# design.net
KiCad netlist of a schematic drawn in Altium Designer
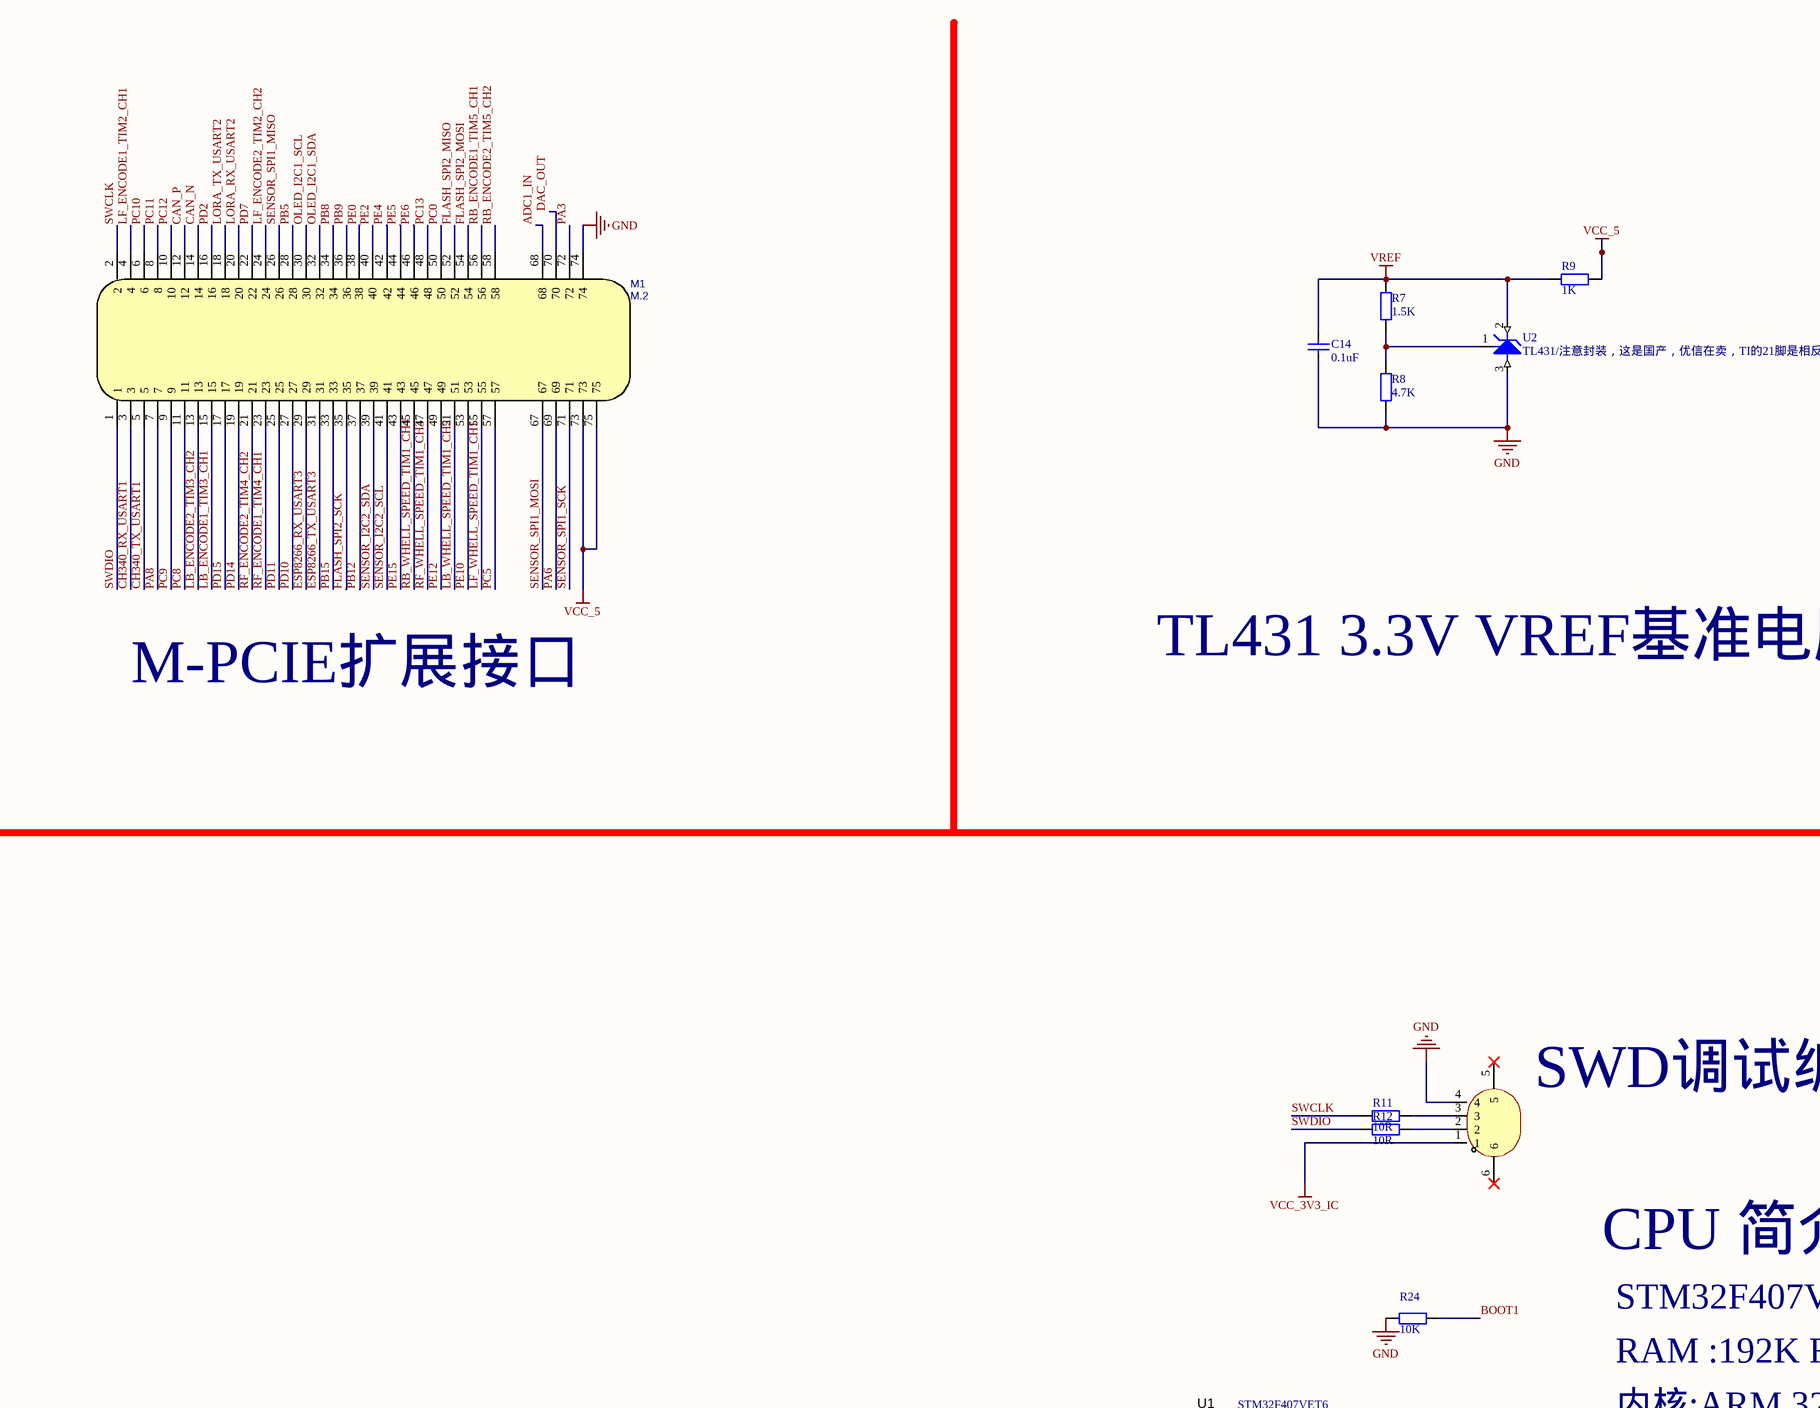
[diagram p0: 主控及低压电源.SchDoc, top left]
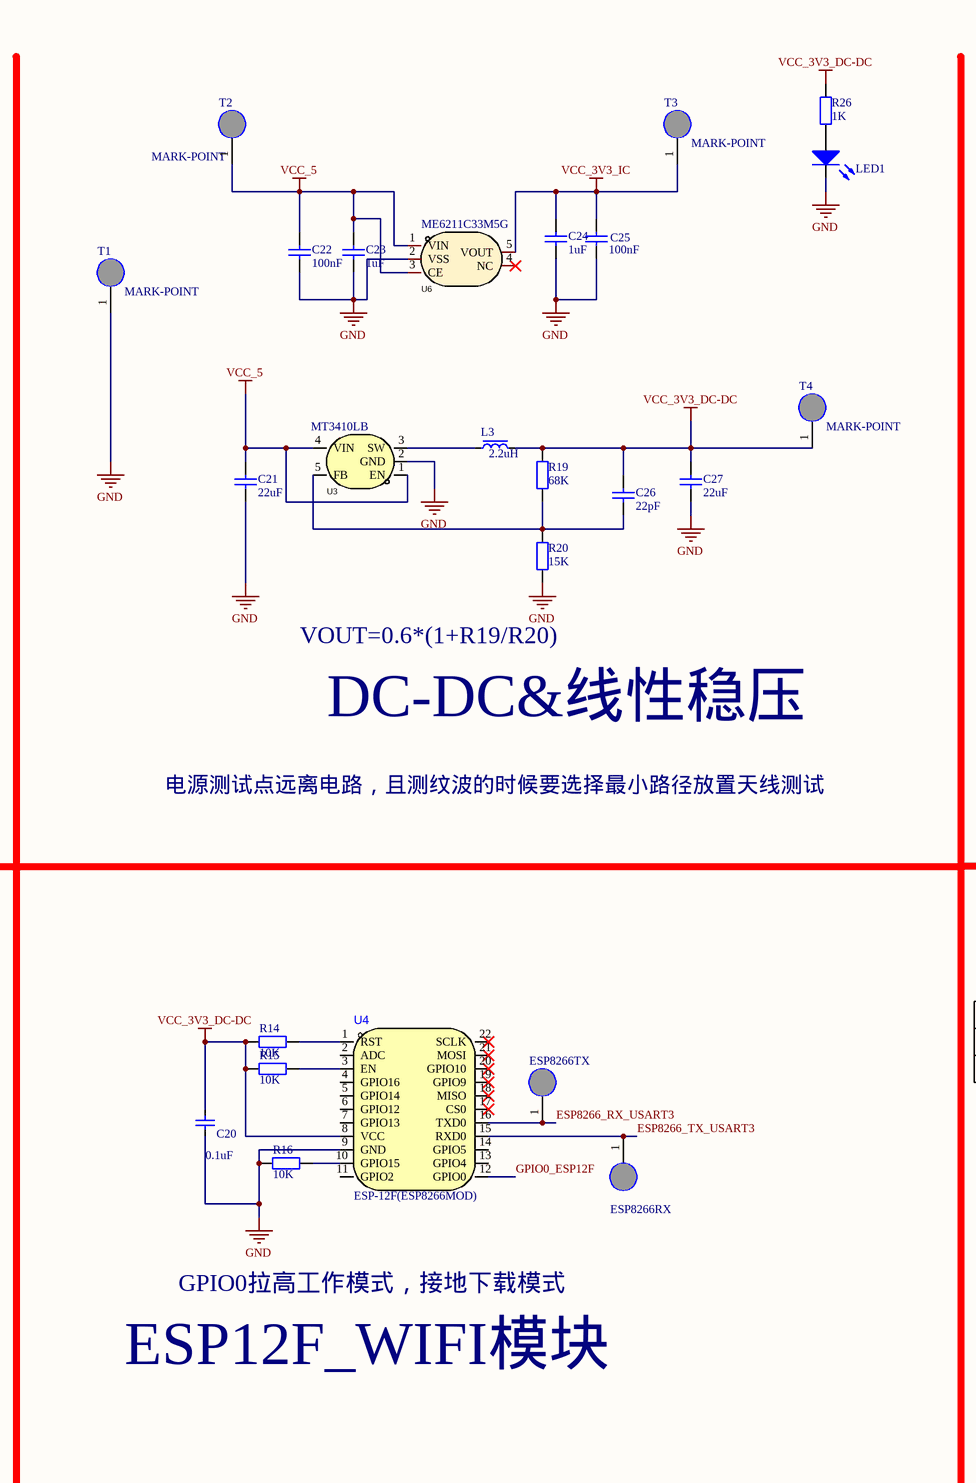
[diagram p1: 主控及低压电源.SchDoc, top middle]
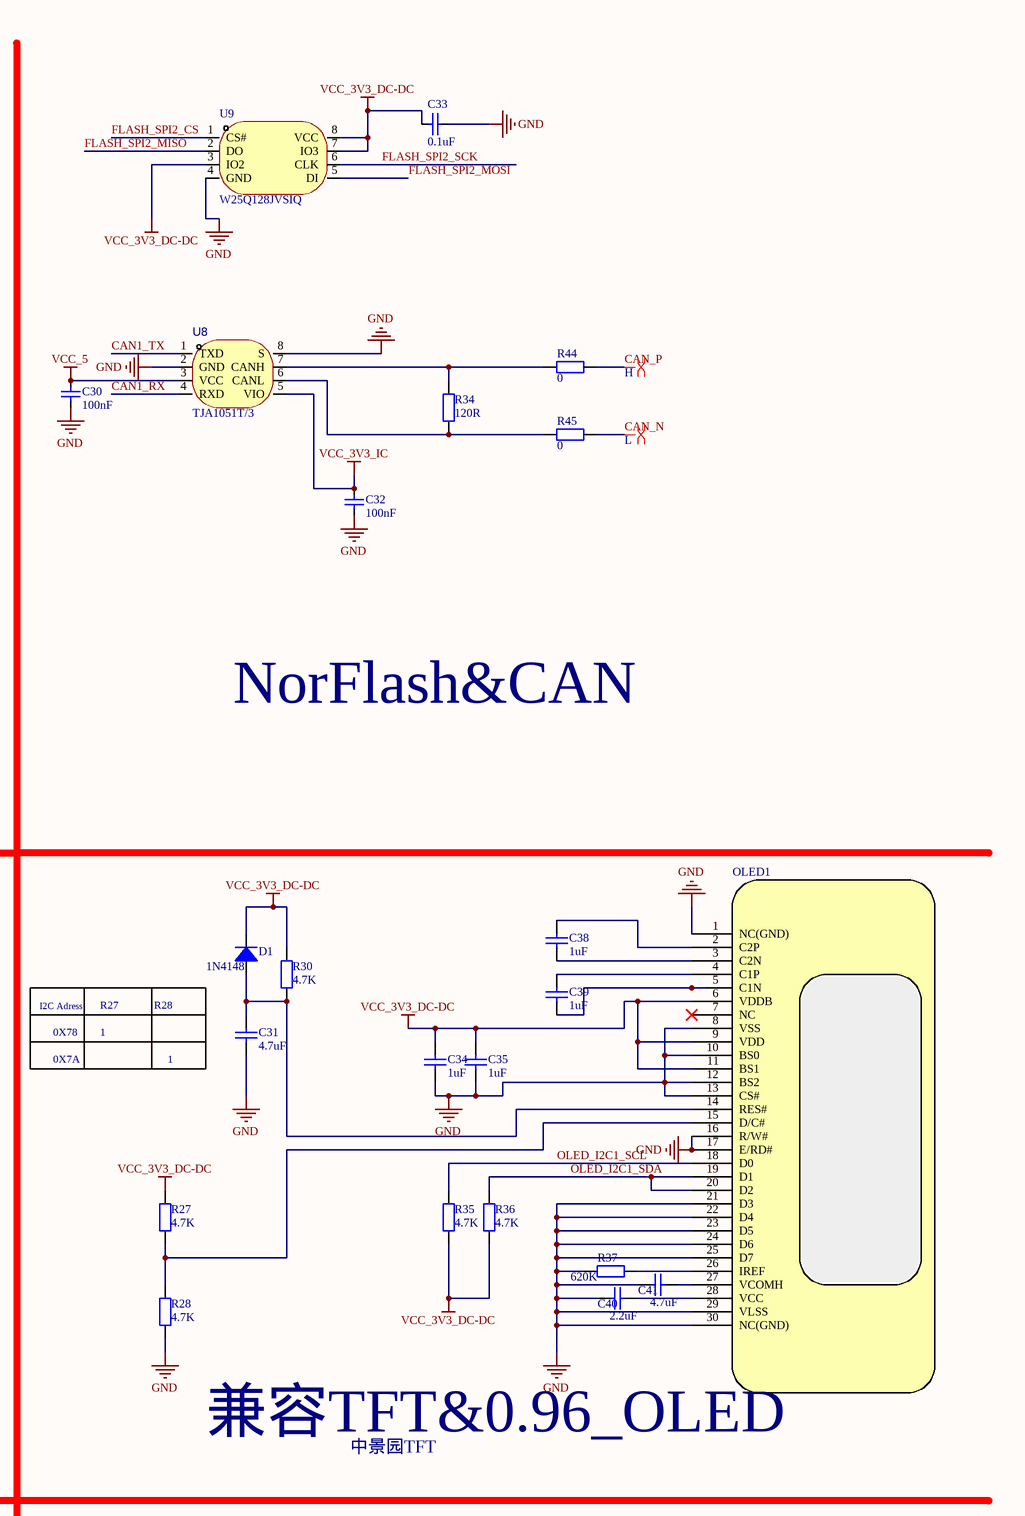
[diagram p2: 主控及低压电源.SchDoc, top right]
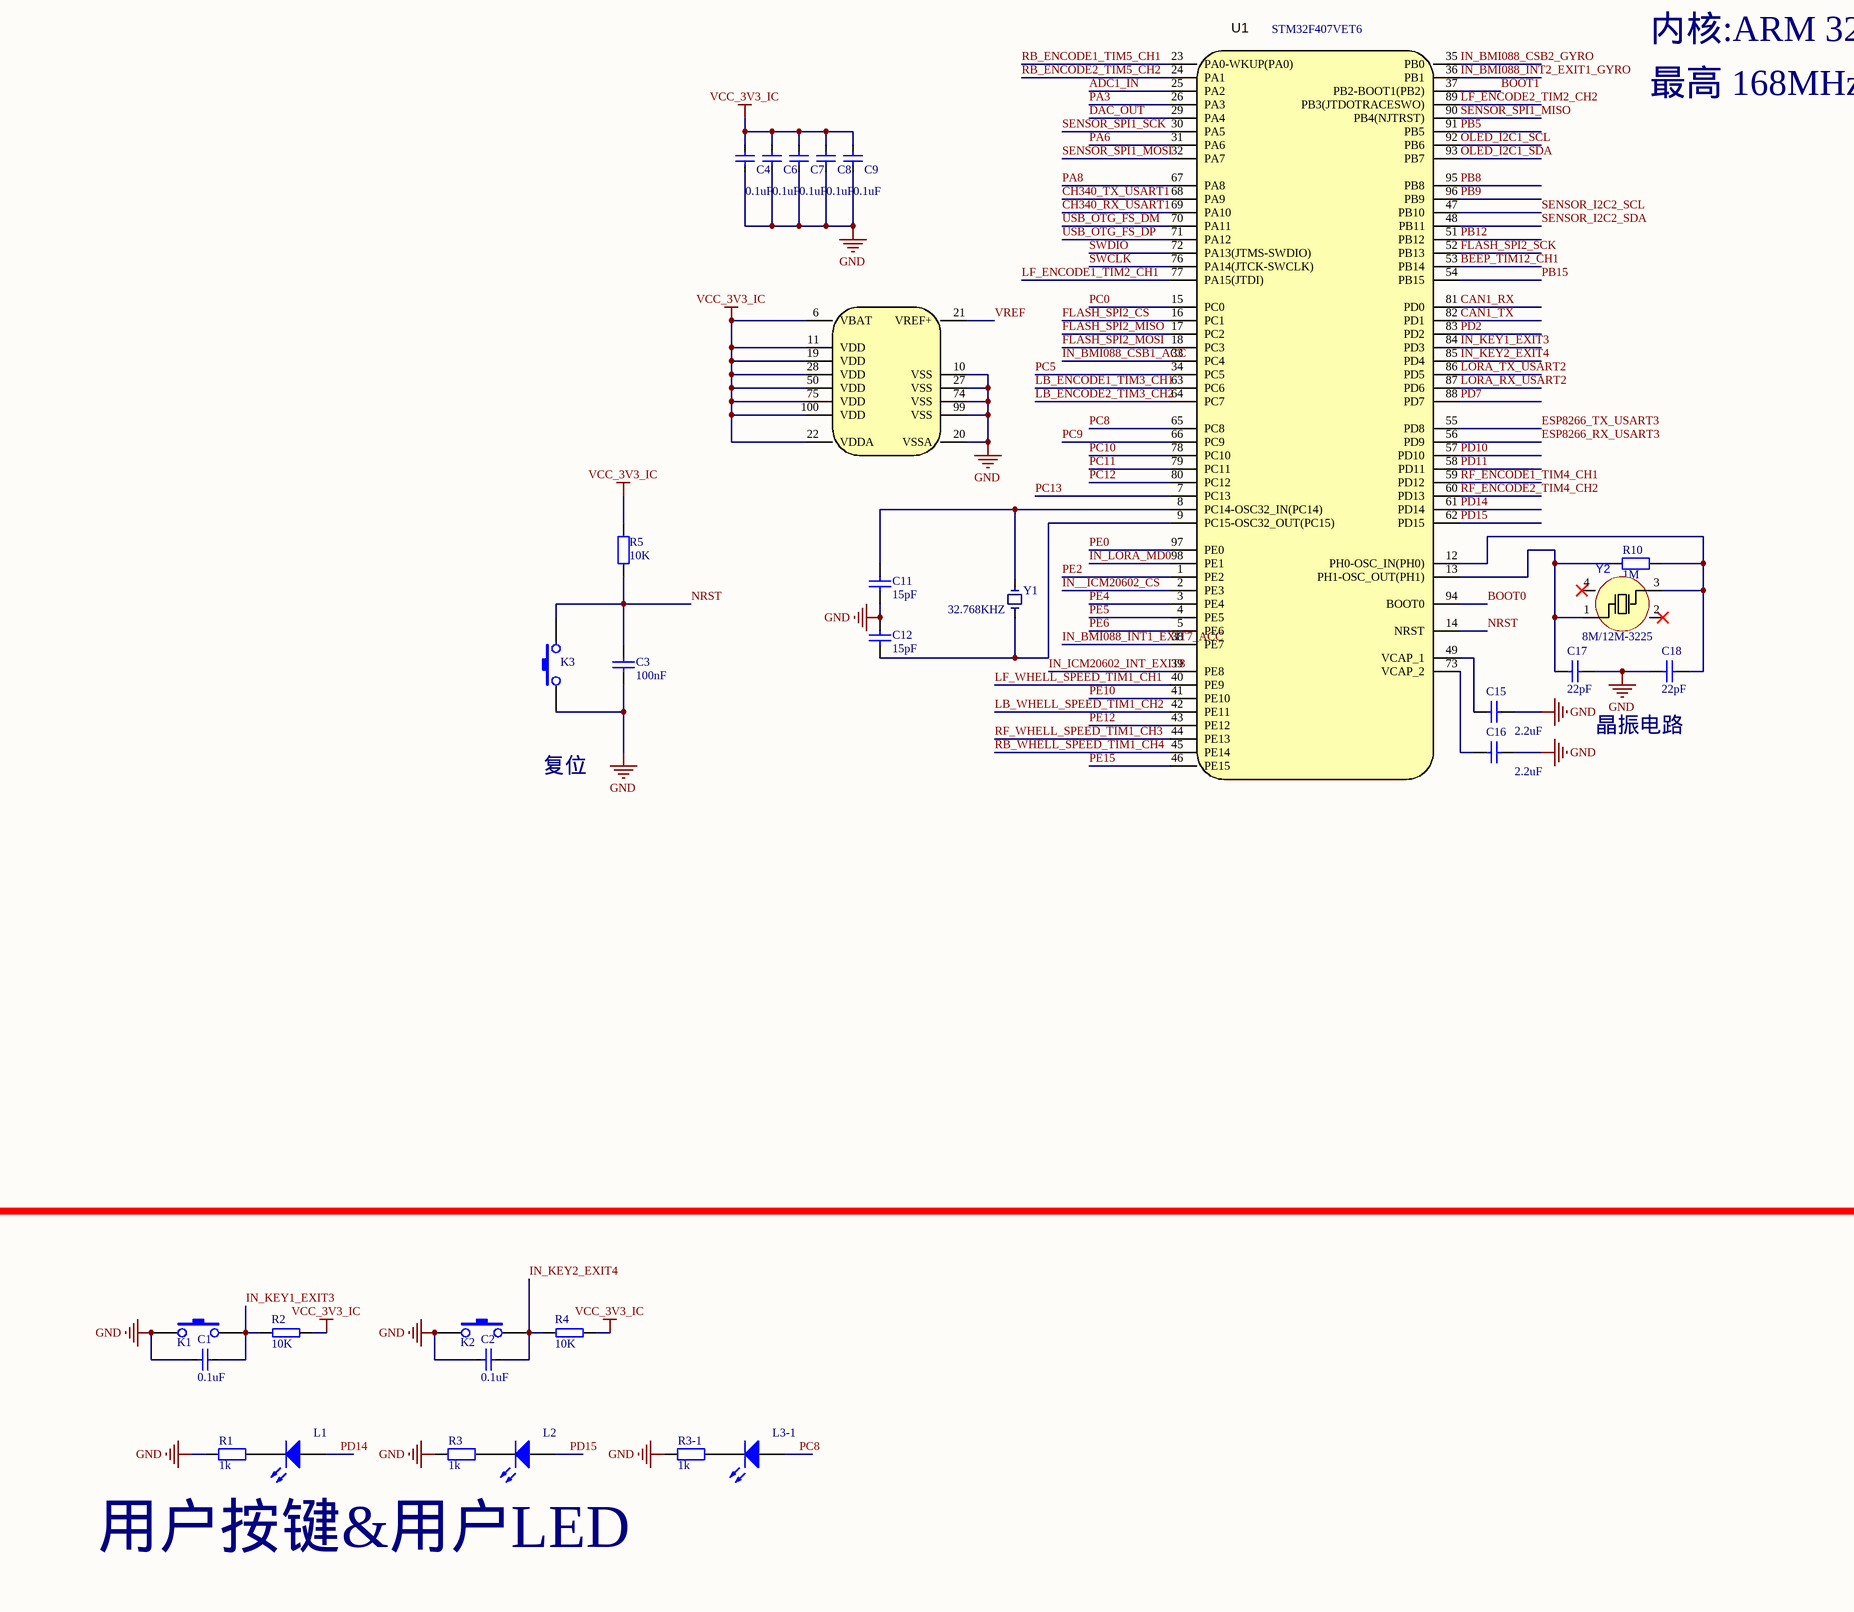
[diagram p3: 主控及低压电源.SchDoc, bottom left]
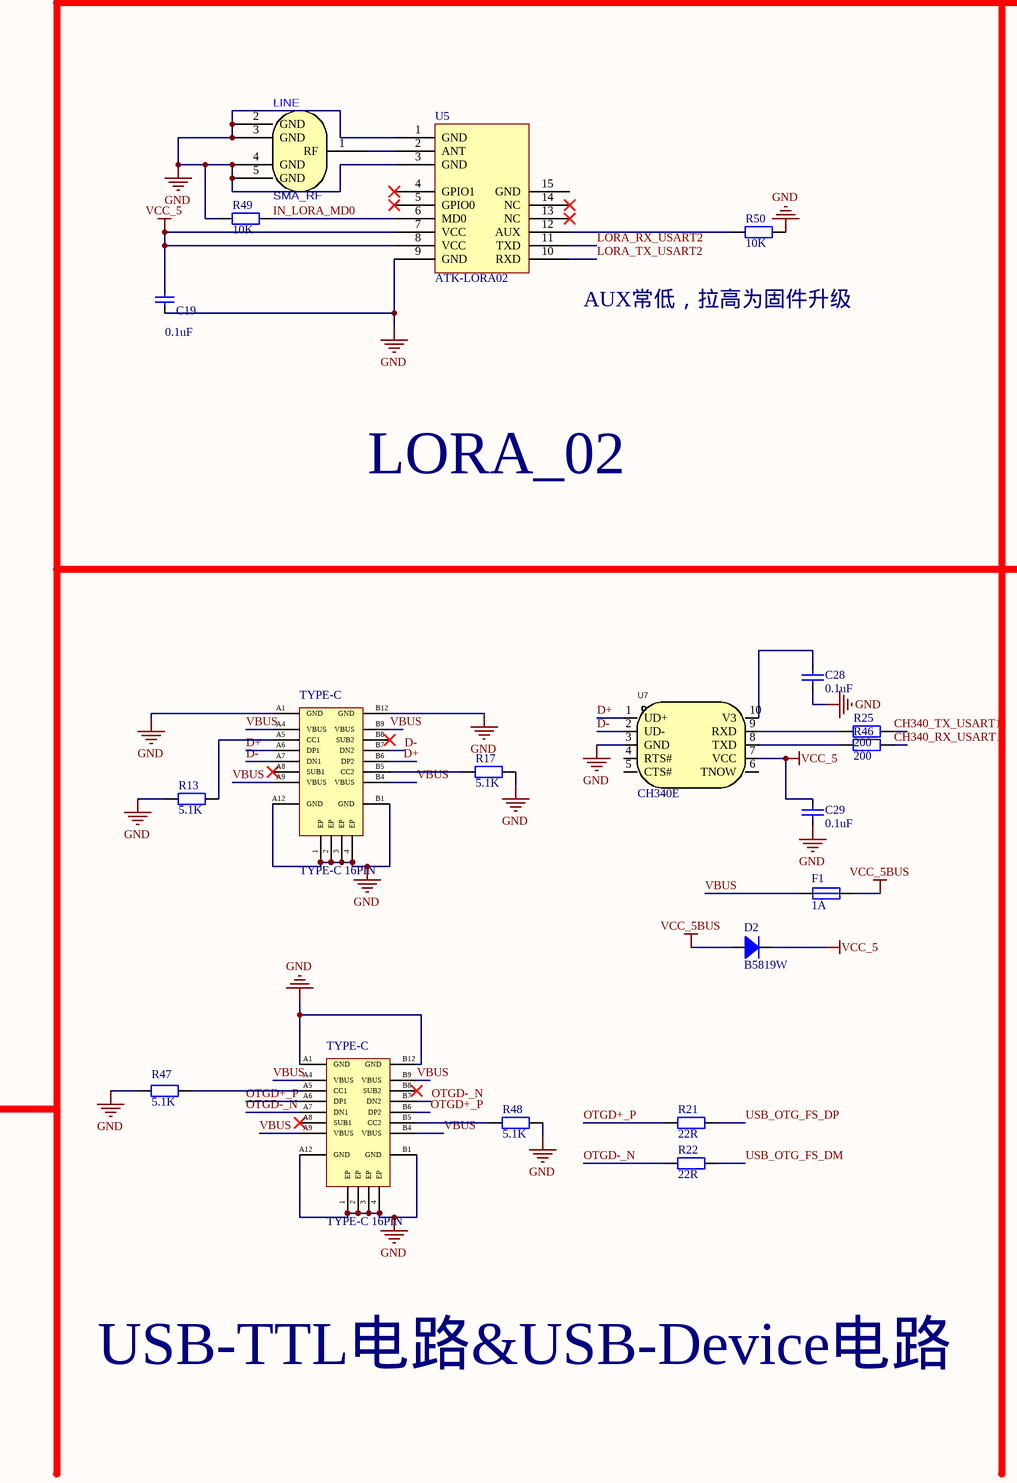
[diagram p4: 主控及低压电源.SchDoc, bottom middle]
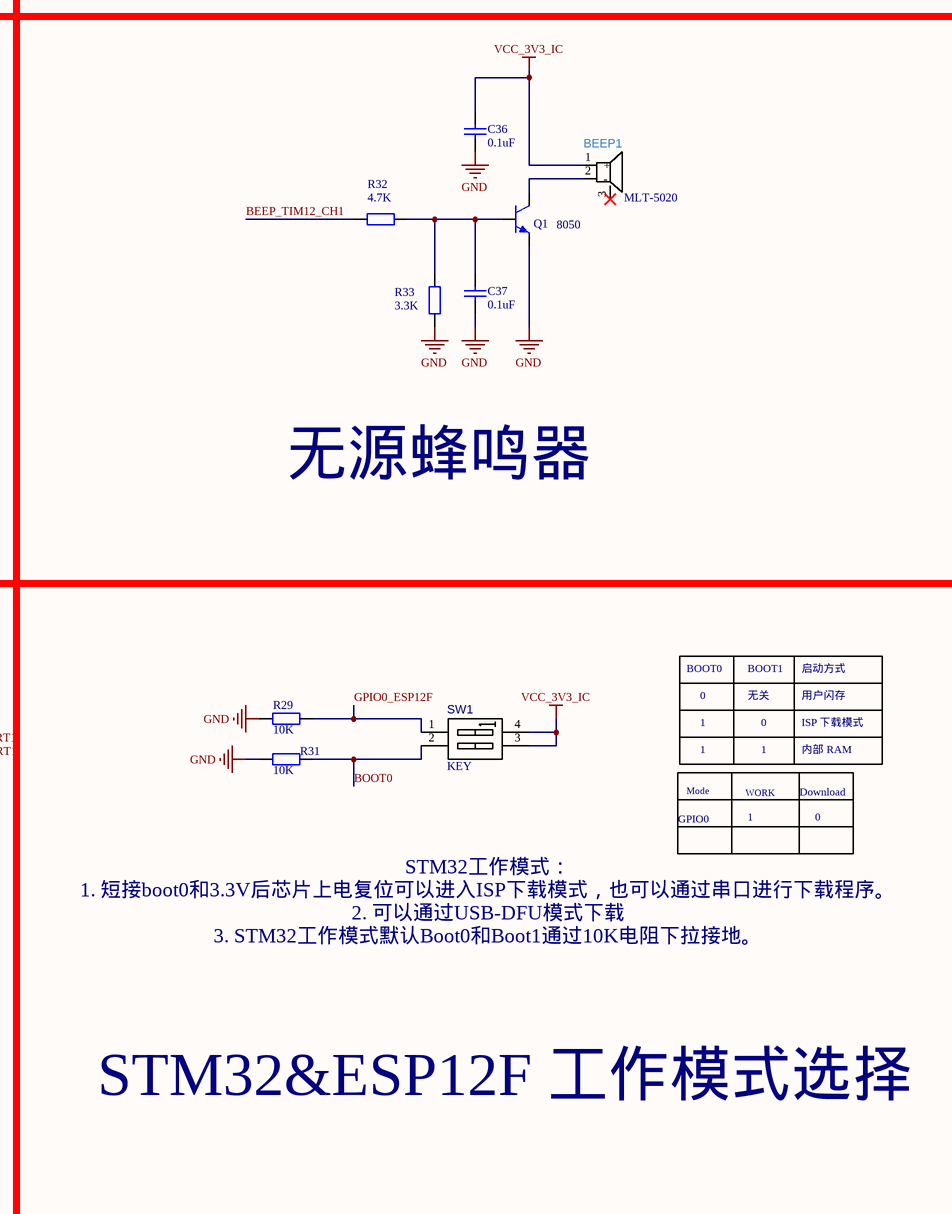
[diagram p5: 主控及低压电源.SchDoc, bottom right]

(export (version "E")
  (design (tool "Eeschema 10.0.6"))
  (components
    (comp (ref "1")
      (value "TYPE-C 16PIN")
      (footprint "TYPE-C 16PIN")
      (libsource (lib "IPC14") (part "TYPE-C 16PIN"))
    )
    (comp (ref "2")
      (value "TYPE-C 16PIN")
      (footprint "TYPE-C 16PIN")
      (libsource (lib "IPC14") (part "TYPE-C 16PIN"))
    )
    (comp (ref "BEEP1")
      (value "MLT-5020")
      (footprint "BUZ-SMD_L5.0-W5.5-P4.60")
      (fields (field (name "MANUFACTURER") "华能"))
      (libsource (lib "KESHE") (part "MLT-5020"))
    )
    (comp (ref "C1")
      (value "0.1uF")
      (footprint "0805_C")
      (description "Capacitor")
      (libsource (lib "SCH_Passive") (part "Cap_0603"))
    )
    (comp (ref "C2")
      (value "0.1uF")
      (footprint "0805_C")
      (description "Capacitor")
      (libsource (lib "SCH_Passive") (part "Cap_0603"))
    )
    (comp (ref "C3")
      (value "100nF")
      (footprint "0603_C")
      (description "Capacitor")
      (libsource (lib "IPC14") (part "CAP"))
    )
    (comp (ref "C4") (value "0.1uF") (footprint "0603_C") (libsource (lib "IPC14(1)") (part "CAP1")))
    (comp (ref "C6") (value "0.1uF") (footprint "0603_C") (libsource (lib "IPC14(1)") (part "CAP1")))
    (comp (ref "C7") (value "0.1uF") (footprint "0603_C") (libsource (lib "IPC14(1)") (part "CAP1")))
    (comp (ref "C8") (value "0.1uF") (footprint "0603_C") (libsource (lib "IPC14(1)") (part "CAP1")))
    (comp (ref "C9") (value "0.1uF") (footprint "0603_C") (libsource (lib "IPC14(1)") (part "CAP1")))
    (comp (ref "C11")
      (value "15pF")
      (footprint "0603_C")
      (description "Capacitor")
      (libsource (lib "IPC14") (part "CAP"))
    )
    (comp (ref "C12")
      (value "15pF")
      (footprint "0603_C")
      (description "Capacitor")
      (libsource (lib "IPC14") (part "CAP"))
    )
    (comp (ref "C14")
      (value "0.1uF")
      (footprint "0603_C")
      (description "Capacitor")
      (libsource (lib "SCH_Passive") (part "Cap_0805"))
    )
    (comp (ref "C15")
      (value "2.2uF")
      (footprint "0603_C")
      (description "Capacitor")
      (libsource (lib "IPC14") (part "CAP"))
    )
    (comp (ref "C16")
      (value "2.2uF")
      (footprint "0603_C")
      (description "Capacitor")
      (libsource (lib "IPC14") (part "CAP"))
    )
    (comp (ref "C17")
      (value "22pF")
      (footprint "0603_C")
      (description "Capacitor")
      (libsource (lib "IPC14") (part "CAP"))
    )
    (comp (ref "C18")
      (value "22pF")
      (footprint "0603_C")
      (description "Capacitor")
      (libsource (lib "IPC14") (part "CAP"))
    )
    (comp (ref "C19") (value "0.1uF") (footprint "0603_C") (libsource (lib "IPC14(1)") (part "CAP1")))
    (comp (ref "C20") (value "0.1uF") (footprint "0603_C") (libsource (lib "IPC14(1)") (part "CAP1")))
    (comp (ref "C21")
      (value "22uF")
      (footprint "0603_C")
      (description "Capacitor")
      (libsource (lib "IPC14") (part "CAP"))
    )
    (comp (ref "C22")
      (value "100nF")
      (footprint "0805C")
      (description "Capacitor")
      (libsource (lib "IPC14") (part "CAP"))
    )
    (comp (ref "C23")
      (value "1uF")
      (footprint "0805_C")
      (description "Capacitor")
      (libsource (lib "IPC14") (part "CAP"))
    )
    (comp (ref "C24")
      (value "1uF")
      (footprint "0805_C")
      (description "Capacitor")
      (libsource (lib "IPC14") (part "CAP"))
    )
    (comp (ref "C25")
      (value "100nF")
      (footprint "0805C")
      (description "Capacitor")
      (libsource (lib "IPC14") (part "CAP"))
    )
    (comp (ref "C26")
      (value "22pF")
      (footprint "0603_C")
      (description "Capacitor")
      (libsource (lib "IPC14") (part "CAP"))
    )
    (comp (ref "C27")
      (value "22uF")
      (footprint "1206_C")
      (description "Capacitor")
      (libsource (lib "IPC14") (part "CAP"))
    )
    (comp (ref "C28")
      (value "0.1uF")
      (footprint "0603_C")
      (description "Capacitor")
      (libsource (lib "SCH_Passive") (part "Cap_0805"))
    )
    (comp (ref "C29")
      (value "0.1uF")
      (footprint "0603_C")
      (description "Capacitor")
      (libsource (lib "SCH_Passive") (part "Cap_0805"))
    )
    (comp (ref "C30") (value "100nF") (footprint "0603_C") (libsource (lib "IPC14(1)") (part "CAP1")))
    (comp (ref "C31")
      (value "4.7uF")
      (footprint "0603_C")
      (description "Capacitor")
      (libsource (lib "IPC14") (part "CAP"))
    )
    (comp (ref "C32") (value "100nF") (footprint "0603_C") (libsource (lib "IPC14(1)") (part "CAP1")))
    (comp (ref "C33")
      (value "0.1uF")
      (footprint "0603_C")
      (description "Capacitor")
      (libsource (lib "SCH_Passive") (part "Cap_0603"))
    )
    (comp (ref "C34")
      (value "1uF")
      (footprint "0603_C")
      (description "Capacitor")
      (libsource (lib "IPC14") (part "CAP"))
    )
    (comp (ref "C35")
      (value "1uF")
      (footprint "0603_C")
      (description "Capacitor")
      (libsource (lib "IPC14") (part "CAP"))
    )
    (comp (ref "C36")
      (value "0.1uF")
      (footprint "0603_C")
      (description "Capacitor")
      (libsource (lib "IPC14") (part "CAP"))
    )
    (comp (ref "C37")
      (value "0.1uF")
      (footprint "0603_C")
      (description "Capacitor")
      (libsource (lib "IPC14") (part "CAP"))
    )
    (comp (ref "C38")
      (value "1uF")
      (footprint "0603_C")
      (description "Capacitor")
      (libsource (lib "IPC14") (part "CAP"))
    )
    (comp (ref "C39")
      (value "1uF")
      (footprint "0603_C")
      (description "Capacitor")
      (libsource (lib "IPC14") (part "CAP"))
    )
    (comp (ref "C40")
      (value "2.2uF")
      (footprint "0603_C")
      (description "Capacitor")
      (libsource (lib "IPC14") (part "CAP"))
    )
    (comp (ref "C41")
      (value "4.7uF")
      (footprint "0603_C")
      (description "Capacitor")
      (libsource (lib "IPC14") (part "CAP"))
    )
    (comp (ref "D1") (value "1N4148") (footprint "SOD123") (libsource (lib "IPC14") (part "1N4007")))
    (comp (ref "D2") (value "B5819W") (footprint "SOD123") (libsource (lib "IPC14") (part "1N4007")))
    (comp (ref "ESP8266RX")
      (value "MARK-POINT")
      (footprint "MARK-POINT")
      (libsource (lib "KESHE") (part "MARK-POINT"))
    )
    (comp (ref "ESP8266TX")
      (value "MARK-POINT")
      (footprint "MARK-POINT")
      (libsource (lib "KESHE") (part "MARK-POINT"))
    )
    (comp (ref "F1")
      (value "1A")
      (footprint "FUSE_1206")
      (description "FUSE,Littelfuse")
      (fields (field (name "Comment") "Fuse 1"))
      (libsource (lib "xl_lib_v2") (part "Fuse 1"))
    )
    (comp (ref "J1")
      (value "XH-4P卧贴")
      (footprint "CONN-SMD_2.54-4P-WT")
      (fields (field (name "MANUFACTURER") "BOOMELE(博穆精密)"))
      (libsource (lib "KESHE") (part "XH-4P卧贴"))
    )
    (comp (ref "K1") (value "SW-PB") (footprint "IPC14:key-sop") (libsource (lib "SW开关") (part "SW-PB")))
    (comp (ref "K2") (value "SW-PB") (footprint "IPC14:key-sop") (libsource (lib "SW开关") (part "SW-PB")))
    (comp (ref "K3") (value "SW-PB") (footprint "IPC14:key-sop") (libsource (lib "SW开关") (part "SW-PB")))
    (comp (ref "L1")
      (value "LED0")
      (footprint "0603_LED")
      (description "Typical INFRARED GaAs LED")
      (fields (field (name "PUBLISHER") "Altium Limited"))
      (libsource (lib "Miscellaneous Devices") (part "LED0"))
    )
    (comp (ref "L2")
      (value "LED0")
      (footprint "0603_LED")
      (description "Typical INFRARED GaAs LED")
      (fields (field (name "PUBLISHER") "Altium Limited"))
      (libsource (lib "Miscellaneous Devices") (part "LED0"))
    )
    (comp (ref "L3")
      (value "2.2uH")
      (footprint "SMD")
      (fields (field (name "ALTIUM_UNNAMED_1") "2.2uH"))
      (libsource (lib "电感-SCH") (part "INDUCTANCE"))
    )
    (comp (ref "L3-1")
      (value "LED0")
      (footprint "0603_LED")
      (description "Typical INFRARED GaAs LED")
      (fields (field (name "PUBLISHER") "Altium Limited"))
      (libsource (lib "Miscellaneous Devices") (part "LED0"))
    )
    (comp (ref "LED1")
      (value "LED_0603_BLUE")
      (footprint "0603_LED")
      (description "LED")
      (libsource (lib "IPC14(1)") (part "LED_0603_BLUE"))
    )
    (comp (ref "LINE") (value "SMA_RF") (footprint "SMA_RF偏脚") (libsource (lib "KESHE") (part "SMA_RF")))
    (comp (ref "M1")
      (value "M.2")
      (footprint "M.2 M")
      (fields (field (name "CONTRIBUTOR") "LAXXI"))
      (libsource (lib "KESHE") (part "M.2"))
    )
    (comp (ref "OLED1")
      (value "OLED_0.96_30P")
      (footprint "oled_0.96_30p")
      (fields (field (name "MANUFACTURER") "WiseChip") (field (name "MANUFACTURER PART") "VG-2864KSWEG01"))
      (libsource (lib "KESHE") (part "OLED_0.96_30P"))
    )
    (comp (ref "Q1")
      (value "8050")
      (footprint "SOT_23")
      (description "NPN")
      (libsource (lib "xl_lib_v1") (part "S8050"))
    )
    (comp (ref "R1")
      (value "1k")
      (footprint "0603_R")
      (description "Resistor")
      (fields (field (name "Comment") "1K") (field (name "PUBLISHER") "Altium Limited"))
      (libsource (lib "Miscellaneous Devices") (part "Res2"))
    )
    (comp (ref "R2")
      (value "10K")
      (footprint "0603_R")
      (fields (field (name "ALTIUM_UNNAMED_1") "10K"))
      (libsource (lib "Flyking 常用元件") (part "RES_10K"))
    )
    (comp (ref "R3")
      (value "1k")
      (footprint "0603_R")
      (description "Resistor")
      (fields (field (name "Comment") "1K") (field (name "PUBLISHER") "Altium Limited"))
      (libsource (lib "Miscellaneous Devices") (part "Res2"))
    )
    (comp (ref "R3-1")
      (value "1k")
      (footprint "0603_R")
      (description "Resistor")
      (fields (field (name "Comment") "1K") (field (name "PUBLISHER") "Altium Limited"))
      (libsource (lib "Miscellaneous Devices") (part "Res2"))
    )
    (comp (ref "R4")
      (value "10K")
      (footprint "0603_R")
      (fields (field (name "ALTIUM_UNNAMED_1") "10K"))
      (libsource (lib "Flyking 常用元件") (part "RES_10K"))
    )
    (comp (ref "R5")
      (value "10K")
      (footprint "0603_R")
      (description "Ressitor")
      (libsource (lib "") (part "RES_2"))
    )
    (comp (ref "R7")
      (value "1.5K")
      (footprint "0603_R")
      (description "Ressitor")
      (libsource (lib "") (part "RES_1"))
    )
    (comp (ref "R8")
      (value "4.7K")
      (footprint "0603_R")
      (description "Ressitor")
      (libsource (lib "") (part "RES_1"))
    )
    (comp (ref "R9")
      (value "1K")
      (footprint "0603_R")
      (description "Ressitor")
      (libsource (lib "IPC14") (part "RES"))
    )
    (comp (ref "R10")
      (value "1M")
      (footprint "0603_R")
      (description "Resistor")
      (libsource (lib "SCH_Passive") (part "Res_0603"))
    )
    (comp (ref "R11")
      (value "10R")
      (footprint "0603_R")
      (description "Resistor")
      (libsource (lib "") (part "Res_0603_2"))
    )
    (comp (ref "R12")
      (value "10R")
      (footprint "0603_R")
      (description "Resistor")
      (libsource (lib "") (part "Res_0603_2"))
    )
    (comp (ref "R13")
      (value "5.1K")
      (footprint "0603_R")
      (description "Resistor")
      (libsource (lib "SCH_Passive") (part "Res_0603"))
    )
    (comp (ref "R14")
      (value "10K")
      (footprint "0603_R")
      (description "Ressitor")
      (libsource (lib "") (part "RES_1"))
    )
    (comp (ref "R15")
      (value "10K")
      (footprint "0603_R")
      (description "Ressitor")
      (libsource (lib "") (part "RES_1"))
    )
    (comp (ref "R16")
      (value "10K")
      (footprint "0603_R")
      (description "Ressitor")
      (libsource (lib "") (part "RES_1"))
    )
    (comp (ref "R17")
      (value "5.1K")
      (footprint "0603_R")
      (description "Resistor")
      (libsource (lib "SCH_Passive") (part "Res_0603"))
    )
    (comp (ref "R19")
      (value "68K")
      (footprint "0603_R")
      (description "Ressitor")
      (libsource (lib "") (part "RES_1"))
    )
    (comp (ref "R20")
      (value "15K")
      (footprint "0603_R")
      (description "Ressitor")
      (libsource (lib "") (part "RES_1"))
    )
    (comp (ref "R21")
      (value "22R")
      (footprint "0603_R")
      (description "Resistor")
      (libsource (lib "SCH_Passive") (part "Res_0603"))
    )
    (comp (ref "R22")
      (value "22R")
      (footprint "0603_R")
      (description "Resistor")
      (libsource (lib "SCH_Passive") (part "Res_0603"))
    )
    (comp (ref "R24")
      (value "10K")
      (footprint "0603_R")
      (description "Resistor")
      (libsource (lib "SCH_Passive") (part "Res_0603"))
    )
    (comp (ref "R25")
      (value "200")
      (footprint "0603_R")
      (description "Resistor")
      (fields (field (name "Comment") "200R"))
      (libsource (lib "SCH_Passive") (part "Res_0603"))
    )
    (comp (ref "R26")
      (value "1K")
      (footprint "0603_R")
      (description "Ressitor")
      (libsource (lib "") (part "RES_2"))
    )
    (comp (ref "R27")
      (value "4.7K")
      (footprint "0603_R")
      (description "Ressitor")
      (libsource (lib "IPC14(1)") (part "RES"))
    )
    (comp (ref "R28")
      (value "4.7K")
      (footprint "0603_R")
      (description "Ressitor")
      (libsource (lib "IPC14(1)") (part "RES"))
    )
    (comp (ref "R29")
      (value "10K")
      (footprint "0603_R")
      (description "Resistor")
      (libsource (lib "SCH_Passive") (part "Res_0603"))
    )
    (comp (ref "R30")
      (value "4.7K")
      (footprint "0603_R")
      (description "Ressitor")
      (libsource (lib "IPC14(1)") (part "RES"))
    )
    (comp (ref "R31")
      (value "10K")
      (footprint "0603_R")
      (description "Resistor")
      (libsource (lib "SCH_Passive") (part "Res_0603"))
    )
    (comp (ref "R32")
      (value "4.7K")
      (footprint "0603_R")
      (description "Resistor")
      (libsource (lib "") (part "Res_0603_2"))
    )
    (comp (ref "R33")
      (value "3.3K")
      (footprint "0603_R")
      (description "Resistor")
      (libsource (lib "") (part "Res_0603_1"))
    )
    (comp (ref "R34")
      (value "120R")
      (footprint "0603_R")
      (description "Ressitor")
      (libsource (lib "") (part "RES_2"))
    )
    (comp (ref "R35")
      (value "4.7K")
      (footprint "0603_R")
      (description "Ressitor")
      (libsource (lib "IPC14(1)") (part "RES"))
    )
    (comp (ref "R36")
      (value "4.7K")
      (footprint "0603_R")
      (description "Ressitor")
      (libsource (lib "IPC14(1)") (part "RES"))
    )
    (comp (ref "R37")
      (value "620K")
      (footprint "0603_R")
      (description "Ressitor")
      (libsource (lib "") (part "RES_1"))
    )
    (comp (ref "R44")
      (value "0")
      (footprint "0603_R")
      (description "Resistor")
      (libsource (lib "SCH_Passive") (part "Res_0603"))
    )
    (comp (ref "R45")
      (value "0")
      (footprint "0603_R")
      (description "Resistor")
      (libsource (lib "SCH_Passive") (part "Res_0603"))
    )
    (comp (ref "R46")
      (value "200")
      (footprint "0603_R")
      (description "Resistor")
      (fields (field (name "Comment") "200R"))
      (libsource (lib "SCH_Passive") (part "Res_0603"))
    )
    (comp (ref "R47")
      (value "5.1K")
      (footprint "0603_R")
      (description "Resistor")
      (libsource (lib "SCH_Passive") (part "Res_0603"))
    )
    (comp (ref "R48")
      (value "5.1K")
      (footprint "0603_R")
      (description "Resistor")
      (libsource (lib "SCH_Passive") (part "Res_0603"))
    )
    (comp (ref "R49")
      (value "10K")
      (footprint "0603_R")
      (description "Ressitor")
      (libsource (lib "") (part "RES_1"))
    )
    (comp (ref "R50")
      (value "10K")
      (footprint "0603_R")
      (description "Ressitor")
      (libsource (lib "") (part "RES_1"))
    )
    (comp (ref "SW1")
      (value "KEY")
      (footprint "SW-SMD_4P_DSHP02TSGET")
      (fields (field (name "MANUFACTURER") "YE") (field (name "MANUFACTURER PART") "DSHP02TSGET"))
      (libsource (lib "KESHE") (part "DSHP02TSGET"))
    )
    (comp (ref "T1")
      (value "MARK-POINT")
      (footprint "MARK-POINT")
      (libsource (lib "KESHE") (part "MARK-POINT"))
    )
    (comp (ref "T2")
      (value "MARK-POINT")
      (footprint "MARK-POINT")
      (libsource (lib "KESHE") (part "MARK-POINT"))
    )
    (comp (ref "T3")
      (value "MARK-POINT")
      (footprint "MARK-POINT")
      (libsource (lib "KESHE") (part "MARK-POINT"))
    )
    (comp (ref "T4")
      (value "MARK-POINT")
      (footprint "MARK-POINT")
      (libsource (lib "KESHE") (part "MARK-POINT"))
    )
    (comp (ref "U1")
      (value "STM32F407VET6")
      (footprint "LQF-100PIN")
      (fields (field (name "MANUFACTURER") "ST(意法半导体)"))
      (libsource (lib "KESHE") (part "STM32F407VET6"))
    )
    (comp (ref "U2")
      (value "TL431/注意封装，这是国产，优信在卖，TI的21脚是相反，一切以432的封装为准")
      (footprint "SOT23-3 `")
      (description "IC")
      (libsource (lib "IPC14") (part "TL431"))
    )
    (comp (ref "U3")
      (value "MT3410LB")
      (footprint "SOT23-5")
      (fields (field (name "MANUFACTURER") "西安航天民芯"))
      (libsource (lib "KESHE") (part "MT3410LB"))
    )
    (comp (ref "U4")
      (value "ESP-12F(ESP8266MOD)")
      (footprint "WIFIM-SMD_ESP-12F-ESP8266MOD")
      (fields (field (name "MANUFACTURER") "Ai-Thinker(安信可)"))
      (libsource (lib "KESHE") (part "ESP-12F(ESP8266MOD)"))
    )
    (comp (ref "U5") (value "ATK-LORA02") (footprint "ATK-LORA02") (libsource (lib "KESHE") (part "LORA02")))
    (comp (ref "U6")
      (value "ME6211C33M5G")
      (footprint "SOT23-5")
      (fields (field (name "MANUFACTURER") "MICRONE(南京微盟)") (field (name "MANUFACTURER PART") "ME6211C25M5G"))
      (libsource (lib "ME6211C25M5G1_ME6211C25M5G") (part "ME6211C25M5G"))
    )
    (comp (ref "U7")
      (value "CH340E")
      (footprint "MSOP-10_L3.0-W3.0-P0.50-LS5.0-BL")
      (fields (field (name "MANUFACTURER") "WCH(南京沁恒)"))
      (libsource (lib "KESHE") (part "CH340E"))
    )
    (comp (ref "U8")
      (value "TJA1051T/3")
      (footprint "SOP-8")
      (fields (field (name "MANUFACTURER") "Tokmas(托克马斯)"))
      (libsource (lib "KESHE") (part "TJA1051T/3"))
    )
    (comp (ref "U9")
      (value "W25Q128JVSIQ")
      (footprint "SOIC-8_L5.3-W5.3-P1.27-LS8.0-BL")
      (description "128Mbit(16MBx8bit),高速版,")
      (fields (field (name "MANUFACTURER") "WINBOND(华邦)") (field (name "NAME") "W25Q128JVSIQ"))
      (libsource (lib "KESHE") (part "W25Q128JVSIQ"))
    )
    (comp (ref "Y1")
      (value "32.768KHZ")
      (footprint "OSC-SMD_L3.2-W1.5")
      (description "YST310S")
      (libsource (lib "IPC14") (part "晶振"))
    )
    (comp (ref "Y2")
      (value "8M/12M-3225")
      (footprint "OSC-SMD_4P-L3.2-W2.5-BL")
      (description "无源晶振")
      (fields (field (name "MANUFACTURER") "YXC扬兴科技") (field (name "MANUFACTURER PART") "X322512MSB4SI"))
      (libsource (lib "KESHE") (part "X322512MSB4SI"))
    )
  )
  (nets
    (net (code "1") (name "/ADC1_IN") (class "Default")
      (node (ref "M1") (pin "68") (pinfunction "68_68") (pintype "passive"))
      (node (ref "U1") (pin "25") (pinfunction "PA2_25") (pintype "passive"))
    )
    (net (code "2") (name "/BEEP_TIM12_CH1") (class "Default")
      (node (ref "R32") (pin "1") (pinfunction "1_1") (pintype "passive"))
      (node (ref "U1") (pin "53") (pinfunction "PB14_53") (pintype "passive"))
    )
    (net (code "3") (name "/BOOT0") (class "Default")
      (node (ref "R31") (pin "1") (pinfunction "1_1") (pintype "passive"))
      (node (ref "SW1") (pin "2") (pinfunction "A2_2") (pintype "passive"))
      (node (ref "U1") (pin "94") (pinfunction "BOOT0_94") (pintype "passive"))
    )
    (net (code "4") (name "/BOOT1") (class "Default")
      (node (ref "R24") (pin "1") (pinfunction "1_1") (pintype "passive"))
      (node (ref "U1") (pin "37") (pinfunction "PB2-BOOT1(PB2)_37") (pintype "passive"))
    )
    (net (code "5") (name "/CAN1_RX") (class "Default")
      (node (ref "U1") (pin "81") (pinfunction "PD0_81") (pintype "passive"))
      (node (ref "U8") (pin "4") (pinfunction "RXD_4") (pintype "passive"))
    )
    (net (code "6") (name "/CAN1_TX") (class "Default")
      (node (ref "U1") (pin "82") (pinfunction "PD1_82") (pintype "passive"))
      (node (ref "U8") (pin "1") (pinfunction "TXD_1") (pintype "passive"))
    )
    (net (code "7") (name "/CAN_N") (class "Default")
      (node (ref "M1") (pin "14") (pinfunction "14_14") (pintype "passive"))
      (node (ref "R45") (pin "1") (pinfunction "1_1") (pintype "passive"))
    )
    (net (code "8") (name "/CAN_P") (class "Default")
      (node (ref "M1") (pin "12") (pinfunction "12_12") (pintype "passive"))
      (node (ref "R44") (pin "1") (pinfunction "1_1") (pintype "passive"))
    )
    (net (code "9") (name "/CH340_RX_USART1") (class "Default")
      (node (ref "M1") (pin "3") (pinfunction "3_3") (pintype "passive"))
      (node (ref "R46") (pin "1") (pinfunction "1_1") (pintype "passive"))
      (node (ref "U1") (pin "69") (pinfunction "PA10_69") (pintype "passive"))
    )
    (net (code "10") (name "/CH340_TX_USART1") (class "Default")
      (node (ref "M1") (pin "5") (pinfunction "5_5") (pintype "passive"))
      (node (ref "R25") (pin "1") (pinfunction "1_1") (pintype "passive"))
      (node (ref "U1") (pin "68") (pinfunction "PA9_68") (pintype "passive"))
    )
    (net (code "11") (name "/D+") (class "Default")
      (node (ref "1") (pin "A6") (pinfunction "DP1_A6") (pintype "passive"))
      (node (ref "1") (pin "B6") (pinfunction "DP2_B6") (pintype "passive"))
      (node (ref "U7") (pin "1") (pinfunction "UD+_1") (pintype "passive"))
    )
    (net (code "12") (name "/D-") (class "Default")
      (node (ref "1") (pin "A7") (pinfunction "DN1_A7") (pintype "passive"))
      (node (ref "1") (pin "B7") (pinfunction "DN2_B7") (pintype "passive"))
      (node (ref "U7") (pin "2") (pinfunction "UD-_2") (pintype "passive"))
    )
    (net (code "13") (name "/DAC_OUT") (class "Default")
      (node (ref "M1") (pin "70") (pinfunction "70_70") (pintype "passive"))
      (node (ref "U1") (pin "29") (pinfunction "PA4_29") (pintype "passive"))
    )
    (net (code "14") (name "/ESP8266_RX_USART3") (class "Default")
      (node (ref "ESP8266TX") (pin "1") (pintype "passive"))
      (node (ref "M1") (pin "29") (pinfunction "29_29") (pintype "passive"))
      (node (ref "U1") (pin "56") (pinfunction "PD9_56") (pintype "passive"))
      (node (ref "U4") (pin "16") (pinfunction "TXD0_16") (pintype "passive"))
    )
    (net (code "15") (name "/ESP8266_TX_USART3") (class "Default")
      (node (ref "ESP8266RX") (pin "1") (pintype "passive"))
      (node (ref "M1") (pin "31") (pinfunction "31_31") (pintype "passive"))
      (node (ref "U1") (pin "55") (pinfunction "PD8_55") (pintype "passive"))
      (node (ref "U4") (pin "15") (pinfunction "RXD0_15") (pintype "passive"))
    )
    (net (code "16") (name "/FLASH_SPI2_CS") (class "Default")
      (node (ref "U1") (pin "16") (pinfunction "PC1_16") (pintype "passive"))
      (node (ref "U9") (pin "1") (pinfunction "CS#_1") (pintype "passive"))
    )
    (net (code "17") (name "/FLASH_SPI2_MISO") (class "Default")
      (node (ref "M1") (pin "52") (pinfunction "52_52") (pintype "passive"))
      (node (ref "U1") (pin "17") (pinfunction "PC2_17") (pintype "passive"))
      (node (ref "U9") (pin "2") (pinfunction "DO_2") (pintype "passive"))
    )
    (net (code "18") (name "/FLASH_SPI2_MOSI") (class "Default")
      (node (ref "M1") (pin "54") (pinfunction "54_54") (pintype "passive"))
      (node (ref "U1") (pin "18") (pinfunction "PC3_18") (pintype "passive"))
      (node (ref "U9") (pin "5") (pinfunction "DI_5") (pintype "passive"))
    )
    (net (code "19") (name "/FLASH_SPI2_SCK") (class "Default")
      (node (ref "M1") (pin "35") (pinfunction "35_35") (pintype "passive"))
      (node (ref "U1") (pin "52") (pinfunction "PB13_52") (pintype "passive"))
      (node (ref "U9") (pin "6") (pinfunction "CLK_6") (pintype "passive"))
    )
    (net (code "20") (name "/GPIO0_ESP12F") (class "Default")
      (node (ref "R29") (pin "1") (pinfunction "1_1") (pintype "passive"))
      (node (ref "SW1") (pin "1") (pinfunction "A1_1") (pintype "passive"))
      (node (ref "U4") (pin "12") (pinfunction "GPIO0_12") (pintype "passive"))
    )
    (net (code "21") (name "/IN_BMI088_CSB1_ACC") (class "Default")
      (node (ref "U1") (pin "33") (pinfunction "PC4_33") (pintype "passive"))
    )
    (net (code "22") (name "/IN_BMI088_CSB2_GYRO") (class "Default")
      (node (ref "U1") (pin "35") (pinfunction "PB0_35") (pintype "passive"))
    )
    (net (code "23") (name "/IN_BMI088_INT1_EXIT7_ACC") (class "Default")
      (node (ref "U1") (pin "38") (pinfunction "PE7_38") (pintype "passive"))
    )
    (net (code "24") (name "/IN_BMI088_INT2_EXIT1_GYRO") (class "Default")
      (node (ref "U1") (pin "36") (pinfunction "PB1_36") (pintype "passive"))
    )
    (net (code "25") (name "/IN_ICM20602_INT_EXIT8") (class "Default")
      (node (ref "U1") (pin "39") (pinfunction "PE8_39") (pintype "passive"))
    )
    (net (code "26") (name "/IN_KEY1_EXIT3") (class "Default")
      (node (ref "C1") (pin "2") (pinfunction "2_2") (pintype "passive"))
      (node (ref "K1") (pin "2") (pinfunction "2_2") (pintype "passive"))
      (node (ref "R2") (pin "1") (pintype "passive"))
      (node (ref "U1") (pin "84") (pinfunction "PD3_84") (pintype "passive"))
    )
    (net (code "27") (name "/IN_KEY2_EXIT4") (class "Default")
      (node (ref "C2") (pin "2") (pinfunction "2_2") (pintype "passive"))
      (node (ref "K2") (pin "2") (pinfunction "2_2") (pintype "passive"))
      (node (ref "R4") (pin "1") (pintype "passive"))
      (node (ref "U1") (pin "85") (pinfunction "PD4_85") (pintype "passive"))
    )
    (net (code "28") (name "/IN_LORA_MD0") (class "Default")
      (node (ref "R49") (pin "2") (pinfunction "2_2") (pintype "passive"))
      (node (ref "U1") (pin "98") (pinfunction "PE1_98") (pintype "passive"))
      (node (ref "U5") (pin "6") (pinfunction "MD0_6") (pintype "passive"))
    )
    (net (code "29") (name "/IN__ICM20602_CS") (class "Default")
      (node (ref "U1") (pin "2") (pinfunction "PE3_2") (pintype "passive"))
    )
    (net (code "30") (name "/LB_ENCODE1_TIM3_CH1") (class "Default")
      (node (ref "M1") (pin "15") (pinfunction "15_15") (pintype "passive"))
      (node (ref "U1") (pin "63") (pinfunction "PC6_63") (pintype "passive"))
    )
    (net (code "31") (name "/LB_ENCODE2_TIM3_CH2") (class "Default")
      (node (ref "M1") (pin "13") (pinfunction "13_13") (pintype "passive"))
      (node (ref "U1") (pin "64") (pinfunction "PC7_64") (pintype "passive"))
    )
    (net (code "32") (name "/LB_WHELL_SPEED_TIM1_CH2") (class "Default")
      (node (ref "M1") (pin "51") (pinfunction "51_51") (pintype "passive"))
      (node (ref "U1") (pin "42") (pinfunction "PE11_42") (pintype "passive"))
    )
    (net (code "33") (name "/LF_ENCODE1_TIM2_CH1") (class "Default")
      (node (ref "M1") (pin "4") (pinfunction "4_4") (pintype "passive"))
      (node (ref "U1") (pin "77") (pinfunction "PA15(JTDI)_77") (pintype "passive"))
    )
    (net (code "34") (name "/LF_ENCODE2_TIM2_CH2") (class "Default")
      (node (ref "M1") (pin "24") (pinfunction "24_24") (pintype "passive"))
      (node (ref "U1") (pin "89") (pinfunction "PB3(JTDOTRACESWO)_89") (pintype "passive"))
    )
    (net (code "35") (name "/LF_WHELL_SPEED_TIM1_CH1") (class "Default")
      (node (ref "M1") (pin "55") (pinfunction "55_55") (pintype "passive"))
      (node (ref "U1") (pin "40") (pinfunction "PE9_40") (pintype "passive"))
    )
    (net (code "36") (name "/LORA_RX_USART2") (class "Default")
      (node (ref "M1") (pin "20") (pinfunction "20_20") (pintype "passive"))
      (node (ref "U1") (pin "87") (pinfunction "PD6_87") (pintype "passive"))
      (node (ref "U5") (pin "11") (pinfunction "TXD_11") (pintype "passive"))
    )
    (net (code "37") (name "/LORA_TX_USART2") (class "Default")
      (node (ref "M1") (pin "18") (pinfunction "18_18") (pintype "passive"))
      (node (ref "U1") (pin "86") (pinfunction "PD5_86") (pintype "passive"))
      (node (ref "U5") (pin "10") (pinfunction "RXD_10") (pintype "passive"))
    )
    (net (code "38") (name "/NRST") (class "Default")
      (node (ref "C3") (pin "2") (pinfunction "2_2") (pintype "passive"))
      (node (ref "K3") (pin "2") (pinfunction "2_2") (pintype "passive"))
      (node (ref "R5") (pin "1") (pinfunction "1_1") (pintype "passive"))
      (node (ref "U1") (pin "14") (pinfunction "NRST_14") (pintype "passive"))
    )
    (net (code "39") (name "/OLED_I2C1_SCL") (class "Default")
      (node (ref "M1") (pin "30") (pinfunction "30_30") (pintype "passive"))
      (node (ref "OLED1") (pin "18") (pinfunction "D0_18") (pintype "passive"))
      (node (ref "R35") (pin "2") (pinfunction "2_2") (pintype "passive"))
      (node (ref "U1") (pin "92") (pinfunction "PB6_92") (pintype "passive"))
    )
    (net (code "40") (name "/OLED_I2C1_SDA") (class "Default")
      (node (ref "M1") (pin "32") (pinfunction "32_32") (pintype "passive"))
      (node (ref "OLED1") (pin "19") (pinfunction "D1_19") (pintype "passive"))
      (node (ref "OLED1") (pin "20") (pinfunction "D2_20") (pintype "passive"))
      (node (ref "R36") (pin "2") (pinfunction "2_2") (pintype "passive"))
      (node (ref "U1") (pin "93") (pinfunction "PB7_93") (pintype "passive"))
    )
    (net (code "41") (name "/OTGD+_P") (class "Default")
      (node (ref "2") (pin "A6") (pinfunction "DP1_A6") (pintype "passive"))
      (node (ref "2") (pin "B6") (pinfunction "DP2_B6") (pintype "passive"))
      (node (ref "R21") (pin "2") (pinfunction "2_2") (pintype "passive"))
    )
    (net (code "42") (name "/OTGD-_N") (class "Default")
      (node (ref "2") (pin "A7") (pinfunction "DN1_A7") (pintype "passive"))
      (node (ref "2") (pin "B7") (pinfunction "DN2_B7") (pintype "passive"))
      (node (ref "R22") (pin "2") (pinfunction "2_2") (pintype "passive"))
    )
    (net (code "43") (name "/PA3") (class "Default")
      (node (ref "M1") (pin "72") (pinfunction "72_72") (pintype "passive"))
      (node (ref "U1") (pin "26") (pinfunction "PA3_26") (pintype "passive"))
    )
    (net (code "44") (name "/PA6") (class "Default")
      (node (ref "M1") (pin "69") (pinfunction "69_69") (pintype "passive"))
      (node (ref "U1") (pin "31") (pinfunction "PA6_31") (pintype "passive"))
    )
    (net (code "45") (name "/PA8") (class "Default")
      (node (ref "M1") (pin "7") (pinfunction "7_7") (pintype "passive"))
      (node (ref "U1") (pin "67") (pinfunction "PA8_67") (pintype "passive"))
    )
    (net (code "46") (name "/PB5") (class "Default")
      (node (ref "M1") (pin "28") (pinfunction "28_28") (pintype "passive"))
      (node (ref "U1") (pin "91") (pinfunction "PB5_91") (pintype "passive"))
    )
    (net (code "47") (name "/PB8") (class "Default")
      (node (ref "M1") (pin "34") (pinfunction "34_34") (pintype "passive"))
      (node (ref "U1") (pin "95") (pinfunction "PB8_95") (pintype "passive"))
    )
    (net (code "48") (name "/PB9") (class "Default")
      (node (ref "M1") (pin "36") (pinfunction "36_36") (pintype "passive"))
      (node (ref "U1") (pin "96") (pinfunction "PB9_96") (pintype "passive"))
    )
    (net (code "49") (name "/PB12") (class "Default")
      (node (ref "M1") (pin "37") (pinfunction "37_37") (pintype "passive"))
      (node (ref "U1") (pin "51") (pinfunction "PB12_51") (pintype "passive"))
    )
    (net (code "50") (name "/PB15") (class "Default")
      (node (ref "M1") (pin "33") (pinfunction "33_33") (pintype "passive"))
      (node (ref "U1") (pin "54") (pinfunction "PB15_54") (pintype "passive"))
    )
    (net (code "51") (name "/PC0") (class "Default")
      (node (ref "M1") (pin "50") (pinfunction "50_50") (pintype "passive"))
      (node (ref "U1") (pin "15") (pinfunction "PC0_15") (pintype "passive"))
    )
    (net (code "52") (name "/PC5") (class "Default")
      (node (ref "M1") (pin "57") (pinfunction "57_57") (pintype "passive"))
      (node (ref "U1") (pin "34") (pinfunction "PC5_34") (pintype "passive"))
    )
    (net (code "53") (name "/PC8") (class "Default")
      (node (ref "L3-1") (pin "1") (pinfunction "A_1") (pintype "passive"))
      (node (ref "M1") (pin "11") (pinfunction "11_11") (pintype "passive"))
      (node (ref "U1") (pin "65") (pinfunction "PC8_65") (pintype "passive"))
    )
    (net (code "54") (name "/PC9") (class "Default")
      (node (ref "M1") (pin "9") (pinfunction "9_9") (pintype "passive"))
      (node (ref "U1") (pin "66") (pinfunction "PC9_66") (pintype "passive"))
    )
    (net (code "55") (name "/PC10") (class "Default")
      (node (ref "M1") (pin "6") (pinfunction "6_6") (pintype "passive"))
      (node (ref "U1") (pin "78") (pinfunction "PC10_78") (pintype "passive"))
    )
    (net (code "56") (name "/PC11") (class "Default")
      (node (ref "M1") (pin "8") (pinfunction "8_8") (pintype "passive"))
      (node (ref "U1") (pin "79") (pinfunction "PC11_79") (pintype "passive"))
    )
    (net (code "57") (name "/PC12") (class "Default")
      (node (ref "M1") (pin "10") (pinfunction "10_10") (pintype "passive"))
      (node (ref "U1") (pin "80") (pinfunction "PC12_80") (pintype "passive"))
    )
    (net (code "58") (name "/PC13") (class "Default")
      (node (ref "M1") (pin "48") (pinfunction "48_48") (pintype "passive"))
      (node (ref "U1") (pin "7") (pinfunction "PC13_7") (pintype "passive"))
    )
    (net (code "59") (name "/PD2") (class "Default")
      (node (ref "M1") (pin "16") (pinfunction "16_16") (pintype "passive"))
      (node (ref "U1") (pin "83") (pinfunction "PD2_83") (pintype "passive"))
    )
    (net (code "60") (name "/PD7") (class "Default")
      (node (ref "M1") (pin "22") (pinfunction "22_22") (pintype "passive"))
      (node (ref "U1") (pin "88") (pinfunction "PD7_88") (pintype "passive"))
    )
    (net (code "61") (name "/PD10") (class "Default")
      (node (ref "M1") (pin "27") (pinfunction "27_27") (pintype "passive"))
      (node (ref "U1") (pin "57") (pinfunction "PD10_57") (pintype "passive"))
    )
    (net (code "62") (name "/PD11") (class "Default")
      (node (ref "M1") (pin "25") (pinfunction "25_25") (pintype "passive"))
      (node (ref "U1") (pin "58") (pinfunction "PD11_58") (pintype "passive"))
    )
    (net (code "63") (name "/PD14") (class "Default")
      (node (ref "L1") (pin "1") (pinfunction "A_1") (pintype "passive"))
      (node (ref "M1") (pin "19") (pinfunction "19_19") (pintype "passive"))
      (node (ref "U1") (pin "61") (pinfunction "PD14_61") (pintype "passive"))
    )
    (net (code "64") (name "/PD15") (class "Default")
      (node (ref "L2") (pin "1") (pinfunction "A_1") (pintype "passive"))
      (node (ref "M1") (pin "17") (pinfunction "17_17") (pintype "passive"))
      (node (ref "U1") (pin "62") (pinfunction "PD15_62") (pintype "passive"))
    )
    (net (code "65") (name "/PE0") (class "Default")
      (node (ref "M1") (pin "38") (pinfunction "38_38") (pintype "passive"))
      (node (ref "U1") (pin "97") (pinfunction "PE0_97") (pintype "passive"))
    )
    (net (code "66") (name "/PE2") (class "Default")
      (node (ref "M1") (pin "40") (pinfunction "40_40") (pintype "passive"))
      (node (ref "U1") (pin "1") (pinfunction "PE2_1") (pintype "passive"))
    )
    (net (code "67") (name "/PE4") (class "Default")
      (node (ref "M1") (pin "42") (pinfunction "42_42") (pintype "passive"))
      (node (ref "U1") (pin "3") (pinfunction "PE4_3") (pintype "passive"))
    )
    (net (code "68") (name "/PE5") (class "Default")
      (node (ref "M1") (pin "44") (pinfunction "44_44") (pintype "passive"))
      (node (ref "U1") (pin "4") (pinfunction "PE5_4") (pintype "passive"))
    )
    (net (code "69") (name "/PE6") (class "Default")
      (node (ref "M1") (pin "46") (pinfunction "46_46") (pintype "passive"))
      (node (ref "U1") (pin "5") (pinfunction "PE6_5") (pintype "passive"))
    )
    (net (code "70") (name "/PE10") (class "Default")
      (node (ref "M1") (pin "53") (pinfunction "53_53") (pintype "passive"))
      (node (ref "U1") (pin "41") (pinfunction "PE10_41") (pintype "passive"))
    )
    (net (code "71") (name "/PE12") (class "Default")
      (node (ref "M1") (pin "49") (pinfunction "49_49") (pintype "passive"))
      (node (ref "U1") (pin "43") (pinfunction "PE12_43") (pintype "passive"))
    )
    (net (code "72") (name "/PE15") (class "Default")
      (node (ref "M1") (pin "43") (pinfunction "43_43") (pintype "passive"))
      (node (ref "U1") (pin "46") (pinfunction "PE15_46") (pintype "passive"))
    )
    (net (code "73") (name "/RB_ENCODE1_TIM5_CH1") (class "Default")
      (node (ref "M1") (pin "56") (pinfunction "56_56") (pintype "passive"))
      (node (ref "U1") (pin "23") (pinfunction "PA0-WKUP(PA0)_23") (pintype "passive"))
    )
    (net (code "74") (name "/RB_ENCODE2_TIM5_CH2") (class "Default")
      (node (ref "M1") (pin "58") (pinfunction "58_58") (pintype "passive"))
      (node (ref "U1") (pin "24") (pinfunction "PA1_24") (pintype "passive"))
    )
    (net (code "75") (name "/RB_WHELL_SPEED_TIM1_CH4") (class "Default")
      (node (ref "M1") (pin "45") (pinfunction "45_45") (pintype "passive"))
      (node (ref "U1") (pin "45") (pinfunction "PE14_45") (pintype "passive"))
    )
    (net (code "76") (name "/RF_ENCODE1_TIM4_CH1") (class "Default")
      (node (ref "M1") (pin "23") (pinfunction "23_23") (pintype "passive"))
      (node (ref "U1") (pin "59") (pinfunction "PD12_59") (pintype "passive"))
    )
    (net (code "77") (name "/RF_ENCODE2_TIM4_CH2") (class "Default")
      (node (ref "M1") (pin "21") (pinfunction "21_21") (pintype "passive"))
      (node (ref "U1") (pin "60") (pinfunction "PD13_60") (pintype "passive"))
    )
    (net (code "78") (name "/RF_WHELL_SPEED_TIM1_CH3") (class "Default")
      (node (ref "M1") (pin "47") (pinfunction "47_47") (pintype "passive"))
      (node (ref "U1") (pin "44") (pinfunction "PE13_44") (pintype "passive"))
    )
    (net (code "79") (name "/SENSOR_I2C2_SCL") (class "Default")
      (node (ref "M1") (pin "41") (pinfunction "41_41") (pintype "passive"))
      (node (ref "U1") (pin "47") (pinfunction "PB10_47") (pintype "passive"))
    )
    (net (code "80") (name "/SENSOR_I2C2_SDA") (class "Default")
      (node (ref "M1") (pin "39") (pinfunction "39_39") (pintype "passive"))
      (node (ref "U1") (pin "48") (pinfunction "PB11_48") (pintype "passive"))
    )
    (net (code "81") (name "/SENSOR_SPI1_MISO") (class "Default")
      (node (ref "M1") (pin "26") (pinfunction "26_26") (pintype "passive"))
      (node (ref "U1") (pin "90") (pinfunction "PB4(NJTRST)_90") (pintype "passive"))
    )
    (net (code "82") (name "/SENSOR_SPI1_MOSI") (class "Default")
      (node (ref "M1") (pin "67") (pinfunction "67_67") (pintype "passive"))
      (node (ref "U1") (pin "32") (pinfunction "PA7_32") (pintype "passive"))
    )
    (net (code "83") (name "/SENSOR_SPI1_SCK") (class "Default")
      (node (ref "M1") (pin "71") (pinfunction "71_71") (pintype "passive"))
      (node (ref "U1") (pin "30") (pinfunction "PA5_30") (pintype "passive"))
    )
    (net (code "84") (name "/SWCLK") (class "Default")
      (node (ref "M1") (pin "2") (pinfunction "2_2") (pintype "passive"))
      (node (ref "R11") (pin "1") (pinfunction "1_1") (pintype "passive"))
      (node (ref "U1") (pin "76") (pinfunction "PA14(JTCK-SWCLK)_76") (pintype "passive"))
    )
    (net (code "85") (name "/SWDIO") (class "Default")
      (node (ref "M1") (pin "1") (pinfunction "1_1") (pintype "passive"))
      (node (ref "R12") (pin "1") (pinfunction "1_1") (pintype "passive"))
      (node (ref "U1") (pin "72") (pinfunction "PA13(JTMS-SWDIO)_72") (pintype "passive"))
    )
    (net (code "86") (name "/USB_OTG_FS_DM") (class "Default")
      (node (ref "R22") (pin "1") (pinfunction "1_1") (pintype "passive"))
      (node (ref "U1") (pin "70") (pinfunction "PA11_70") (pintype "passive"))
    )
    (net (code "87") (name "/USB_OTG_FS_DP") (class "Default")
      (node (ref "R21") (pin "1") (pinfunction "1_1") (pintype "passive"))
      (node (ref "U1") (pin "71") (pinfunction "PA12_71") (pintype "passive"))
    )
    (net (code "88") (name "/VBUS") (class "Default")
      (node (ref "1") (pin "A4") (pinfunction "VBUS_A4") (pintype "passive"))
      (node (ref "1") (pin "A9") (pinfunction "VBUS_A9") (pintype "passive"))
      (node (ref "1") (pin "B4") (pinfunction "VBUS_B4") (pintype "passive"))
      (node (ref "1") (pin "B9") (pinfunction "VBUS_B9") (pintype "passive"))
      (node (ref "2") (pin "A4") (pinfunction "VBUS_A4") (pintype "passive"))
      (node (ref "2") (pin "A9") (pinfunction "VBUS_A9") (pintype "passive"))
      (node (ref "2") (pin "B4") (pinfunction "VBUS_B4") (pintype "passive"))
      (node (ref "2") (pin "B9") (pinfunction "VBUS_B9") (pintype "passive"))
      (node (ref "F1") (pin "1") (pinfunction "IN+_1") (pintype "passive"))
    )
    (net (code "89") (name "GND") (class "Default")
      (node (ref "1") (pin "1") (pinfunction "EP_1") (pintype "passive"))
      (node (ref "1") (pin "2") (pinfunction "EP_2") (pintype "passive"))
      (node (ref "1") (pin "3") (pinfunction "EP_3") (pintype "passive"))
      (node (ref "1") (pin "4") (pinfunction "EP_4") (pintype "passive"))
      (node (ref "1") (pin "A1") (pinfunction "GND_A1") (pintype "passive"))
      (node (ref "1") (pin "A12") (pinfunction "GND_A12") (pintype "passive"))
      (node (ref "1") (pin "B1") (pinfunction "GND_B1") (pintype "passive"))
      (node (ref "1") (pin "B12") (pinfunction "GND_B12") (pintype "passive"))
      (node (ref "2") (pin "1") (pinfunction "EP_1") (pintype "passive"))
      (node (ref "2") (pin "2") (pinfunction "EP_2") (pintype "passive"))
      (node (ref "2") (pin "3") (pinfunction "EP_3") (pintype "passive"))
      (node (ref "2") (pin "4") (pinfunction "EP_4") (pintype "passive"))
      (node (ref "2") (pin "A1") (pinfunction "GND_A1") (pintype "passive"))
      (node (ref "2") (pin "A12") (pinfunction "GND_A12") (pintype "passive"))
      (node (ref "2") (pin "B1") (pinfunction "GND_B1") (pintype "passive"))
      (node (ref "2") (pin "B12") (pinfunction "GND_B12") (pintype "passive"))
      (node (ref "C1") (pin "1") (pinfunction "1_1") (pintype "passive"))
      (node (ref "C11") (pin "1") (pinfunction "1_1") (pintype "passive"))
      (node (ref "C12") (pin "1") (pinfunction "1_1") (pintype "passive"))
      (node (ref "C14") (pin "1") (pinfunction "1_1") (pintype "passive"))
      (node (ref "C15") (pin "2") (pinfunction "2_2") (pintype "passive"))
      (node (ref "C16") (pin "2") (pinfunction "2_2") (pintype "passive"))
      (node (ref "C17") (pin "2") (pinfunction "2_2") (pintype "passive"))
      (node (ref "C18") (pin "1") (pinfunction "1_1") (pintype "passive"))
      (node (ref "C19") (pin "2") (pintype "passive"))
      (node (ref "C2") (pin "1") (pinfunction "1_1") (pintype "passive"))
      (node (ref "C20") (pin "2") (pintype "passive"))
      (node (ref "C21") (pin "1") (pinfunction "1_1") (pintype "passive"))
      (node (ref "C22") (pin "1") (pinfunction "1_1") (pintype "passive"))
      (node (ref "C23") (pin "1") (pinfunction "1_1") (pintype "passive"))
      (node (ref "C24") (pin "1") (pinfunction "1_1") (pintype "passive"))
      (node (ref "C25") (pin "1") (pinfunction "1_1") (pintype "passive"))
      (node (ref "C27") (pin "1") (pinfunction "1_1") (pintype "passive"))
      (node (ref "C28") (pin "1") (pinfunction "1_1") (pintype "passive"))
      (node (ref "C29") (pin "1") (pinfunction "1_1") (pintype "passive"))
      (node (ref "C3") (pin "1") (pinfunction "1_1") (pintype "passive"))
      (node (ref "C30") (pin "1") (pintype "passive"))
      (node (ref "C31") (pin "1") (pinfunction "1_1") (pintype "passive"))
      (node (ref "C32") (pin "1") (pintype "passive"))
      (node (ref "C33") (pin "2") (pinfunction "2_2") (pintype "passive"))
      (node (ref "C34") (pin "1") (pinfunction "1_1") (pintype "passive"))
      (node (ref "C35") (pin "1") (pinfunction "1_1") (pintype "passive"))
      (node (ref "C36") (pin "2") (pinfunction "2_2") (pintype "passive"))
      (node (ref "C37") (pin "2") (pinfunction "2_2") (pintype "passive"))
      (node (ref "C4") (pin "2") (pintype "passive"))
      (node (ref "C40") (pin "2") (pinfunction "2_2") (pintype "passive"))
      (node (ref "C41") (pin "2") (pinfunction "2_2") (pintype "passive"))
      (node (ref "C6") (pin "2") (pintype "passive"))
      (node (ref "C7") (pin "2") (pintype "passive"))
      (node (ref "C8") (pin "2") (pintype "passive"))
      (node (ref "C9") (pin "2") (pintype "passive"))
      (node (ref "J1") (pin "4") (pinfunction "4_4") (pintype "passive"))
      (node (ref "K1") (pin "1") (pinfunction "1_1") (pintype "passive"))
      (node (ref "K2") (pin "1") (pinfunction "1_1") (pintype "passive"))
      (node (ref "K3") (pin "1") (pinfunction "1_1") (pintype "passive"))
      (node (ref "LED1") (pin "2") (pinfunction "K_2") (pintype "passive"))
      (node (ref "LINE") (pin "2") (pinfunction "GND_2") (pintype "passive"))
      (node (ref "LINE") (pin "3") (pinfunction "GND_3") (pintype "passive"))
      (node (ref "LINE") (pin "4") (pinfunction "GND_4") (pintype "passive"))
      (node (ref "LINE") (pin "5") (pinfunction "GND_5") (pintype "passive"))
      (node (ref "M1") (pin "74") (pinfunction "74_74") (pintype "passive"))
      (node (ref "OLED1") (pin "1") (pinfunction "NC(GND)_1") (pintype "passive"))
      (node (ref "OLED1") (pin "10") (pinfunction "BS0_10") (pintype "passive"))
      (node (ref "OLED1") (pin "12") (pinfunction "BS2_12") (pintype "passive"))
      (node (ref "OLED1") (pin "13") (pinfunction "CS#_13") (pintype "passive"))
      (node (ref "OLED1") (pin "16") (pinfunction "R/W#_16") (pintype "passive"))
      (node (ref "OLED1") (pin "17") (pinfunction "E/RD#_17") (pintype "passive"))
      (node (ref "OLED1") (pin "21") (pinfunction "D3_21") (pintype "passive"))
      (node (ref "OLED1") (pin "22") (pinfunction "D4_22") (pintype "passive"))
      (node (ref "OLED1") (pin "23") (pinfunction "D5_23") (pintype "passive"))
      (node (ref "OLED1") (pin "24") (pinfunction "D6_24") (pintype "passive"))
      (node (ref "OLED1") (pin "25") (pinfunction "D7_25") (pintype "passive"))
      (node (ref "OLED1") (pin "29") (pinfunction "VLSS_29") (pintype "passive"))
      (node (ref "OLED1") (pin "30") (pinfunction "NC(GND)_30") (pintype "passive"))
      (node (ref "OLED1") (pin "8") (pinfunction "VSS_8") (pintype "passive"))
      (node (ref "Q1") (pin "2") (pinfunction "E_2") (pintype "passive"))
      (node (ref "R1") (pin "1") (pinfunction "1_1") (pintype "passive"))
      (node (ref "R13") (pin "2") (pinfunction "2_2") (pintype "passive"))
      (node (ref "R16") (pin "1") (pinfunction "1_1") (pintype "passive"))
      (node (ref "R17") (pin "1") (pinfunction "1_1") (pintype "passive"))
      (node (ref "R20") (pin "2") (pinfunction "2_2") (pintype "passive"))
      (node (ref "R24") (pin "2") (pinfunction "2_2") (pintype "passive"))
      (node (ref "R28") (pin "1") (pinfunction "1_1") (pintype "passive"))
      (node (ref "R29") (pin "2") (pinfunction "2_2") (pintype "passive"))
      (node (ref "R3") (pin "1") (pinfunction "1_1") (pintype "passive"))
      (node (ref "R3-1") (pin "1") (pinfunction "1_1") (pintype "passive"))
      (node (ref "R31") (pin "2") (pinfunction "2_2") (pintype "passive"))
      (node (ref "R33") (pin "1") (pinfunction "1_1") (pintype "passive"))
      (node (ref "R37") (pin "1") (pinfunction "1_1") (pintype "passive"))
      (node (ref "R47") (pin "2") (pinfunction "2_2") (pintype "passive"))
      (node (ref "R48") (pin "1") (pinfunction "1_1") (pintype "passive"))
      (node (ref "R49") (pin "1") (pinfunction "1_1") (pintype "passive"))
      (node (ref "R50") (pin "2") (pinfunction "2_2") (pintype "passive"))
      (node (ref "R8") (pin "2") (pinfunction "2_2") (pintype "passive"))
      (node (ref "T1") (pin "1") (pintype "passive"))
      (node (ref "U1") (pin "10") (pinfunction "VSS_10") (pintype "passive"))
      (node (ref "U1") (pin "20") (pinfunction "VSSA_20") (pintype "passive"))
      (node (ref "U1") (pin "27") (pinfunction "VSS_27") (pintype "passive"))
      (node (ref "U1") (pin "74") (pinfunction "VSS_74") (pintype "passive"))
      (node (ref "U1") (pin "99") (pinfunction "VSS_99") (pintype "passive"))
      (node (ref "U2") (pin "3") (pinfunction "A_3") (pintype "input"))
      (node (ref "U3") (pin "2") (pinfunction "GND_2") (pintype "passive"))
      (node (ref "U4") (pin "9") (pinfunction "GND_9") (pintype "passive"))
      (node (ref "U5") (pin "1") (pinfunction "GND_1") (pintype "passive"))
      (node (ref "U5") (pin "3") (pinfunction "GND_3") (pintype "passive"))
      (node (ref "U5") (pin "9") (pinfunction "GND_9") (pintype "passive"))
      (node (ref "U6") (pin "2") (pinfunction "VSS_2") (pintype "passive"))
      (node (ref "U7") (pin "3") (pinfunction "GND_3") (pintype "passive"))
      (node (ref "U8") (pin "2") (pinfunction "GND_2") (pintype "passive"))
      (node (ref "U8") (pin "8") (pinfunction "S_8") (pintype "passive"))
      (node (ref "U9") (pin "4") (pinfunction "GND_4") (pintype "passive"))
    )
    (net (code "90") (name "Net-(1-CC1)") (class "Default")
      (node (ref "1") (pin "A5") (pinfunction "CC1_A5") (pintype "passive"))
      (node (ref "R13") (pin "1") (pinfunction "1_1") (pintype "passive"))
    )
    (net (code "91") (name "Net-(1-CC2)") (class "Default")
      (node (ref "1") (pin "B5") (pinfunction "CC2_B5") (pintype "passive"))
      (node (ref "R17") (pin "2") (pinfunction "2_2") (pintype "passive"))
    )
    (net (code "92") (name "Net-(2-CC1)") (class "Default")
      (node (ref "2") (pin "A5") (pinfunction "CC1_A5") (pintype "passive"))
      (node (ref "R47") (pin "1") (pinfunction "1_1") (pintype "passive"))
    )
    (net (code "93") (name "Net-(2-CC2)") (class "Default")
      (node (ref "2") (pin "B5") (pinfunction "CC2_B5") (pintype "passive"))
      (node (ref "R48") (pin "2") (pinfunction "2_2") (pintype "passive"))
    )
    (net (code "94") (name "Net-(BEEP1--)") (class "Default")
      (node (ref "BEEP1") (pin "2") (pinfunction "-_2") (pintype "passive"))
      (node (ref "Q1") (pin "3") (pinfunction "C_3") (pintype "passive"))
    )
    (net (code "95") (name "Net-(D1-A)") (class "Default")
      (node (ref "C31") (pin "2") (pinfunction "2_2") (pintype "passive"))
      (node (ref "D1") (pin "1") (pinfunction "A_1") (pintype "passive"))
      (node (ref "OLED1") (pin "14") (pinfunction "RES#_14") (pintype "passive"))
      (node (ref "R30") (pin "1") (pinfunction "1_1") (pintype "passive"))
    )
    (net (code "96") (name "Net-(J1-Pad2)") (class "Default")
      (node (ref "J1") (pin "2") (pinfunction "2_2") (pintype "passive"))
      (node (ref "R12") (pin "2") (pinfunction "2_2") (pintype "passive"))
    )
    (net (code "97") (name "Net-(J1-Pad3)") (class "Default")
      (node (ref "J1") (pin "3") (pinfunction "3_3") (pintype "passive"))
      (node (ref "R11") (pin "2") (pinfunction "2_2") (pintype "passive"))
    )
    (net (code "98") (name "Net-(L1-K)") (class "Default")
      (node (ref "L1") (pin "2") (pinfunction "K_2") (pintype "passive"))
      (node (ref "R1") (pin "2") (pinfunction "2_2") (pintype "passive"))
    )
    (net (code "99") (name "Net-(L2-K)") (class "Default")
      (node (ref "L2") (pin "2") (pinfunction "K_2") (pintype "passive"))
      (node (ref "R3") (pin "2") (pinfunction "2_2") (pintype "passive"))
    )
    (net (code "100") (name "Net-(L3-1-K)") (class "Default")
      (node (ref "L3-1") (pin "2") (pinfunction "K_2") (pintype "passive"))
      (node (ref "R3-1") (pin "2") (pinfunction "2_2") (pintype "passive"))
    )
    (net (code "101") (name "Net-(LED1-A)") (class "Default")
      (node (ref "LED1") (pin "1") (pinfunction "A_1") (pintype "passive"))
      (node (ref "R26") (pin "1") (pinfunction "1_1") (pintype "passive"))
    )
    (net (code "102") (name "Net-(LINE-RF)") (class "Default")
      (node (ref "LINE") (pin "1") (pinfunction "RF_1") (pintype "passive"))
      (node (ref "U5") (pin "2") (pinfunction "ANT_2") (pintype "passive"))
    )
    (net (code "103") (name "Net-(OLED1-C1N)") (class "Default")
      (node (ref "C39") (pin "1") (pinfunction "1_1") (pintype "passive"))
      (node (ref "OLED1") (pin "5") (pinfunction "C1N_5") (pintype "passive"))
    )
    (net (code "104") (name "Net-(OLED1-C1P)") (class "Default")
      (node (ref "C39") (pin "2") (pinfunction "2_2") (pintype "passive"))
      (node (ref "OLED1") (pin "4") (pinfunction "C1P_4") (pintype "passive"))
    )
    (net (code "105") (name "Net-(OLED1-C2N)") (class "Default")
      (node (ref "C38") (pin "1") (pinfunction "1_1") (pintype "passive"))
      (node (ref "OLED1") (pin "3") (pinfunction "C2N_3") (pintype "passive"))
    )
    (net (code "106") (name "Net-(OLED1-C2P)") (class "Default")
      (node (ref "C38") (pin "2") (pinfunction "2_2") (pintype "passive"))
      (node (ref "OLED1") (pin "2") (pinfunction "C2P_2") (pintype "passive"))
    )
    (net (code "107") (name "Net-(OLED1-D{slash}C#)") (class "Default")
      (node (ref "OLED1") (pin "15") (pinfunction "D/C#_15") (pintype "passive"))
      (node (ref "R27") (pin "1") (pinfunction "1_1") (pintype "passive"))
      (node (ref "R28") (pin "2") (pinfunction "2_2") (pintype "passive"))
    )
    (net (code "108") (name "Net-(OLED1-IREF)") (class "Default")
      (node (ref "OLED1") (pin "26") (pinfunction "IREF_26") (pintype "passive"))
      (node (ref "R37") (pin "2") (pinfunction "2_2") (pintype "passive"))
    )
    (net (code "109") (name "Net-(OLED1-VCC)") (class "Default")
      (node (ref "C40") (pin "1") (pinfunction "1_1") (pintype "passive"))
      (node (ref "OLED1") (pin "28") (pinfunction "VCC_28") (pintype "passive"))
    )
    (net (code "110") (name "Net-(OLED1-VCOMH)") (class "Default")
      (node (ref "C41") (pin "1") (pinfunction "1_1") (pintype "passive"))
      (node (ref "OLED1") (pin "27") (pinfunction "VCOMH_27") (pintype "passive"))
    )
    (net (code "111") (name "Net-(Q1-B)") (class "Default")
      (node (ref "C37") (pin "1") (pinfunction "1_1") (pintype "passive"))
      (node (ref "Q1") (pin "1") (pinfunction "B_1") (pintype "passive"))
      (node (ref "R32") (pin "2") (pinfunction "2_2") (pintype "passive"))
      (node (ref "R33") (pin "2") (pinfunction "2_2") (pintype "passive"))
    )
    (net (code "112") (name "Net-(U1-PC14-OSC32_IN(PC14))") (class "Default")
      (node (ref "C11") (pin "2") (pinfunction "2_2") (pintype "passive"))
      (node (ref "U1") (pin "8") (pinfunction "PC14-OSC32_IN(PC14)_8") (pintype "passive"))
      (node (ref "Y1") (pin "1") (pinfunction "1_1") (pintype "passive"))
    )
    (net (code "113") (name "Net-(U1-PC15-OSC32_OUT(PC15))") (class "Default")
      (node (ref "C12") (pin "2") (pinfunction "2_2") (pintype "passive"))
      (node (ref "U1") (pin "9") (pinfunction "PC15-OSC32_OUT(PC15)_9") (pintype "passive"))
      (node (ref "Y1") (pin "2") (pinfunction "2_2") (pintype "passive"))
    )
    (net (code "114") (name "Net-(U1-PH0-OSC_IN(PH0))") (class "Default")
      (node (ref "C18") (pin "2") (pinfunction "2_2") (pintype "passive"))
      (node (ref "R10") (pin "1") (pinfunction "1_1") (pintype "passive"))
      (node (ref "U1") (pin "12") (pinfunction "PH0-OSC_IN(PH0)_12") (pintype "passive"))
      (node (ref "Y2") (pin "3") (pinfunction "OSC2_3") (pintype "passive"))
    )
    (net (code "115") (name "Net-(U1-PH1-OSC_OUT(PH1))") (class "Default")
      (node (ref "C17") (pin "1") (pinfunction "1_1") (pintype "passive"))
      (node (ref "R10") (pin "2") (pinfunction "2_2") (pintype "passive"))
      (node (ref "U1") (pin "13") (pinfunction "PH1-OSC_OUT(PH1)_13") (pintype "passive"))
      (node (ref "Y2") (pin "1") (pinfunction "OSC1_1") (pintype "passive"))
    )
    (net (code "116") (name "Net-(U1-VCAP_1)") (class "Default")
      (node (ref "C15") (pin "1") (pinfunction "1_1") (pintype "passive"))
      (node (ref "U1") (pin "49") (pinfunction "VCAP_1_49") (pintype "passive"))
    )
    (net (code "117") (name "Net-(U1-VCAP_2)") (class "Default")
      (node (ref "C16") (pin "1") (pinfunction "1_1") (pintype "passive"))
      (node (ref "U1") (pin "73") (pinfunction "VCAP_2_73") (pintype "passive"))
    )
    (net (code "118") (name "Net-(U2-R)") (class "Default")
      (node (ref "R7") (pin "2") (pinfunction "2_2") (pintype "passive"))
      (node (ref "R8") (pin "1") (pinfunction "1_1") (pintype "passive"))
      (node (ref "U2") (pin "1") (pinfunction "R_1") (pintype "passive"))
    )
    (net (code "119") (name "Net-(U3-FB)") (class "Default")
      (node (ref "C26") (pin "1") (pinfunction "1_1") (pintype "passive"))
      (node (ref "R19") (pin "2") (pinfunction "2_2") (pintype "passive"))
      (node (ref "R20") (pin "1") (pinfunction "1_1") (pintype "passive"))
      (node (ref "U3") (pin "5") (pinfunction "FB_5") (pintype "passive"))
    )
    (net (code "120") (name "Net-(U3-SW)") (class "Default")
      (node (ref "L3") (pin "1") (pinfunction "1_1") (pintype "passive"))
      (node (ref "U3") (pin "3") (pinfunction "SW_3") (pintype "passive"))
    )
    (net (code "121") (name "Net-(U4-EN)") (class "Default")
      (node (ref "R15") (pin "2") (pinfunction "2_2") (pintype "passive"))
      (node (ref "U4") (pin "3") (pinfunction "EN_3") (pintype "passive"))
    )
    (net (code "122") (name "Net-(U4-GPIO15)") (class "Default")
      (node (ref "R16") (pin "2") (pinfunction "2_2") (pintype "passive"))
      (node (ref "U4") (pin "10") (pinfunction "GPIO15_10") (pintype "passive"))
    )
    (net (code "123") (name "Net-(U4-RST)") (class "Default")
      (node (ref "R14") (pin "2") (pinfunction "2_2") (pintype "passive"))
      (node (ref "U4") (pin "1") (pinfunction "RST_1") (pintype "passive"))
    )
    (net (code "124") (name "Net-(U5-AUX)") (class "Default")
      (node (ref "R50") (pin "1") (pinfunction "1_1") (pintype "passive"))
      (node (ref "U5") (pin "12") (pinfunction "AUX_12") (pintype "passive"))
    )
    (net (code "125") (name "Net-(U7-RXD)") (class "Default")
      (node (ref "R25") (pin "2") (pinfunction "2_2") (pintype "passive"))
      (node (ref "U7") (pin "9") (pinfunction "RXD_9") (pintype "passive"))
    )
    (net (code "126") (name "Net-(U7-TXD)") (class "Default")
      (node (ref "R46") (pin "2") (pinfunction "2_2") (pintype "passive"))
      (node (ref "U7") (pin "8") (pinfunction "TXD_8") (pintype "passive"))
    )
    (net (code "127") (name "Net-(U7-V3)") (class "Default")
      (node (ref "C28") (pin "2") (pinfunction "2_2") (pintype "passive"))
      (node (ref "U7") (pin "10") (pinfunction "V3_10") (pintype "passive"))
    )
    (net (code "128") (name "Net-(U8-CANH)") (class "Default")
      (node (ref "R34") (pin "1") (pinfunction "1_1") (pintype "passive"))
      (node (ref "R44") (pin "2") (pinfunction "2_2") (pintype "passive"))
      (node (ref "U8") (pin "7") (pinfunction "CANH_7") (pintype "passive"))
    )
    (net (code "129") (name "Net-(U8-CANL)") (class "Default")
      (node (ref "R34") (pin "2") (pinfunction "2_2") (pintype "passive"))
      (node (ref "R45") (pin "2") (pinfunction "2_2") (pintype "passive"))
      (node (ref "U8") (pin "6") (pinfunction "CANL_6") (pintype "passive"))
    )
    (net (code "130") (name "VCC_3V3_DC-DC") (class "Default")
      (node (ref "C20") (pin "1") (pintype "passive"))
      (node (ref "C26") (pin "2") (pinfunction "2_2") (pintype "passive"))
      (node (ref "C27") (pin "2") (pinfunction "2_2") (pintype "passive"))
      (node (ref "C33") (pin "1") (pinfunction "1_1") (pintype "passive"))
      (node (ref "C34") (pin "2") (pinfunction "2_2") (pintype "passive"))
      (node (ref "C35") (pin "2") (pinfunction "2_2") (pintype "passive"))
      (node (ref "D1") (pin "2") (pinfunction "K_2") (pintype "passive"))
      (node (ref "L3") (pin "2") (pinfunction "2_2") (pintype "passive"))
      (node (ref "OLED1") (pin "11") (pinfunction "BS1_11") (pintype "passive"))
      (node (ref "OLED1") (pin "6") (pinfunction "VDDB_6") (pintype "passive"))
      (node (ref "OLED1") (pin "9") (pinfunction "VDD_9") (pintype "passive"))
      (node (ref "R14") (pin "1") (pinfunction "1_1") (pintype "passive"))
      (node (ref "R15") (pin "1") (pinfunction "1_1") (pintype "passive"))
      (node (ref "R19") (pin "1") (pinfunction "1_1") (pintype "passive"))
      (node (ref "R26") (pin "2") (pinfunction "2_2") (pintype "passive"))
      (node (ref "R27") (pin "2") (pinfunction "2_2") (pintype "passive"))
      (node (ref "R30") (pin "2") (pinfunction "2_2") (pintype "passive"))
      (node (ref "R35") (pin "1") (pinfunction "1_1") (pintype "passive"))
      (node (ref "R36") (pin "1") (pinfunction "1_1") (pintype "passive"))
      (node (ref "T4") (pin "1") (pintype "passive"))
      (node (ref "U4") (pin "8") (pinfunction "VCC_8") (pintype "passive"))
      (node (ref "U9") (pin "3") (pinfunction "IO2_3") (pintype "passive"))
      (node (ref "U9") (pin "7") (pinfunction "IO3_7") (pintype "passive"))
      (node (ref "U9") (pin "8") (pinfunction "VCC_8") (pintype "passive"))
    )
    (net (code "131") (name "VCC_3V3_IC") (class "Default")
      (node (ref "BEEP1") (pin "1") (pinfunction "+_1") (pintype "passive"))
      (node (ref "C24") (pin "2") (pinfunction "2_2") (pintype "passive"))
      (node (ref "C25") (pin "2") (pinfunction "2_2") (pintype "passive"))
      (node (ref "C32") (pin "2") (pintype "passive"))
      (node (ref "C36") (pin "1") (pinfunction "1_1") (pintype "passive"))
      (node (ref "C4") (pin "1") (pintype "passive"))
      (node (ref "C6") (pin "1") (pintype "passive"))
      (node (ref "C7") (pin "1") (pintype "passive"))
      (node (ref "C8") (pin "1") (pintype "passive"))
      (node (ref "C9") (pin "1") (pintype "passive"))
      (node (ref "J1") (pin "1") (pinfunction "1_1") (pintype "passive"))
      (node (ref "R2") (pin "2") (pintype "passive"))
      (node (ref "R4") (pin "2") (pintype "passive"))
      (node (ref "R5") (pin "2") (pinfunction "2_2") (pintype "passive"))
      (node (ref "SW1") (pin "3") (pinfunction "B2_3") (pintype "passive"))
      (node (ref "SW1") (pin "4") (pinfunction "B1_4") (pintype "passive"))
      (node (ref "T3") (pin "1") (pintype "passive"))
      (node (ref "U1") (pin "100") (pinfunction "VDD_100") (pintype "passive"))
      (node (ref "U1") (pin "11") (pinfunction "VDD_11") (pintype "passive"))
      (node (ref "U1") (pin "19") (pinfunction "VDD_19") (pintype "passive"))
      (node (ref "U1") (pin "22") (pinfunction "VDDA_22") (pintype "passive"))
      (node (ref "U1") (pin "28") (pinfunction "VDD_28") (pintype "passive"))
      (node (ref "U1") (pin "50") (pinfunction "VDD_50") (pintype "passive"))
      (node (ref "U1") (pin "6") (pinfunction "VBAT_6") (pintype "passive"))
      (node (ref "U1") (pin "75") (pinfunction "VDD_75") (pintype "passive"))
      (node (ref "U6") (pin "5") (pinfunction "VOUT_5") (pintype "passive"))
      (node (ref "U8") (pin "5") (pinfunction "VIO_5") (pintype "passive"))
    )
    (net (code "132") (name "VCC_5") (class "Default")
      (node (ref "C19") (pin "1") (pintype "passive"))
      (node (ref "C21") (pin "2") (pinfunction "2_2") (pintype "passive"))
      (node (ref "C22") (pin "2") (pinfunction "2_2") (pintype "passive"))
      (node (ref "C23") (pin "2") (pinfunction "2_2") (pintype "passive"))
      (node (ref "C29") (pin "2") (pinfunction "2_2") (pintype "passive"))
      (node (ref "C30") (pin "2") (pintype "passive"))
      (node (ref "D2") (pin "2") (pinfunction "K_2") (pintype "passive"))
      (node (ref "M1") (pin "73") (pinfunction "73_73") (pintype "passive"))
      (node (ref "M1") (pin "75") (pinfunction "75_75") (pintype "passive"))
      (node (ref "R9") (pin "1") (pinfunction "1_1") (pintype "passive"))
      (node (ref "T2") (pin "1") (pintype "passive"))
      (node (ref "U3") (pin "1") (pinfunction "EN_1") (pintype "passive"))
      (node (ref "U3") (pin "4") (pinfunction "VIN_4") (pintype "passive"))
      (node (ref "U5") (pin "7") (pinfunction "VCC_7") (pintype "passive"))
      (node (ref "U5") (pin "8") (pinfunction "VCC_8") (pintype "passive"))
      (node (ref "U6") (pin "1") (pinfunction "VIN_1") (pintype "passive"))
      (node (ref "U6") (pin "3") (pinfunction "CE_3") (pintype "passive"))
      (node (ref "U7") (pin "7") (pinfunction "VCC_7") (pintype "passive"))
      (node (ref "U8") (pin "3") (pinfunction "VCC_3") (pintype "passive"))
    )
    (net (code "133") (name "VCC_5BUS") (class "Default")
      (node (ref "D2") (pin "1") (pinfunction "A_1") (pintype "passive"))
      (node (ref "F1") (pin "2") (pinfunction "IN-_2") (pintype "passive"))
    )
    (net (code "134") (name "VREF") (class "Default")
      (node (ref "C14") (pin "2") (pinfunction "2_2") (pintype "passive"))
      (node (ref "R7") (pin "1") (pinfunction "1_1") (pintype "passive"))
      (node (ref "R9") (pin "2") (pinfunction "2_2") (pintype "passive"))
      (node (ref "U1") (pin "21") (pinfunction "VREF+_21") (pintype "passive"))
      (node (ref "U2") (pin "2") (pinfunction "K_2") (pintype "input"))
    )
    (net (code "135") (name "unconnected-(1-SUB1-PadA8)") (class "Default")
      (node (ref "1") (pin "A8") (pinfunction "SUB1_A8") (pintype "passive+no_connect"))
    )
    (net (code "136") (name "unconnected-(1-SUB2-PadB8)") (class "Default")
      (node (ref "1") (pin "B8") (pinfunction "SUB2_B8") (pintype "passive+no_connect"))
    )
    (net (code "137") (name "unconnected-(2-SUB1-PadA8)") (class "Default")
      (node (ref "2") (pin "A8") (pinfunction "SUB1_A8") (pintype "passive+no_connect"))
    )
    (net (code "138") (name "unconnected-(2-SUB2-PadB8)") (class "Default")
      (node (ref "2") (pin "B8") (pinfunction "SUB2_B8") (pintype "passive+no_connect"))
    )
    (net (code "139") (name "unconnected-(BEEP1-NC-Pad3)") (class "Default")
      (node (ref "BEEP1") (pin "3") (pinfunction "NC_3") (pintype "passive+no_connect"))
    )
    (net (code "140") (name "unconnected-(J1-Pad5)") (class "Default")
      (node (ref "J1") (pin "5") (pinfunction "5_5") (pintype "passive+no_connect"))
    )
    (net (code "141") (name "unconnected-(J1-Pad6)") (class "Default")
      (node (ref "J1") (pin "6") (pinfunction "6_6") (pintype "passive+no_connect"))
    )
    (net (code "142") (name "unconnected-(OLED1-NC-Pad7)") (class "Default")
      (node (ref "OLED1") (pin "7") (pinfunction "NC_7") (pintype "passive+no_connect"))
    )
    (net (code "143") (name "unconnected-(U4-ADC-Pad2)") (class "Default")
      (node (ref "U4") (pin "2") (pinfunction "ADC_2") (pintype "passive"))
    )
    (net (code "144") (name "unconnected-(U4-CS0-Pad17)") (class "Default")
      (node (ref "U4") (pin "17") (pinfunction "CS0_17") (pintype "passive+no_connect"))
    )
    (net (code "145") (name "unconnected-(U4-GPIO2-Pad11)") (class "Default")
      (node (ref "U4") (pin "11") (pinfunction "GPIO2_11") (pintype "passive"))
    )
    (net (code "146") (name "unconnected-(U4-GPIO4-Pad13)") (class "Default")
      (node (ref "U4") (pin "13") (pinfunction "GPIO4_13") (pintype "passive"))
    )
    (net (code "147") (name "unconnected-(U4-GPIO5-Pad14)") (class "Default")
      (node (ref "U4") (pin "14") (pinfunction "GPIO5_14") (pintype "passive"))
    )
    (net (code "148") (name "unconnected-(U4-GPIO9-Pad19)") (class "Default")
      (node (ref "U4") (pin "19") (pinfunction "GPIO9_19") (pintype "passive+no_connect"))
    )
    (net (code "149") (name "unconnected-(U4-GPIO10-Pad20)") (class "Default")
      (node (ref "U4") (pin "20") (pinfunction "GPIO10_20") (pintype "passive+no_connect"))
    )
    (net (code "150") (name "unconnected-(U4-GPIO12-Pad6)") (class "Default")
      (node (ref "U4") (pin "6") (pinfunction "GPIO12_6") (pintype "passive"))
    )
    (net (code "151") (name "unconnected-(U4-GPIO13-Pad7)") (class "Default")
      (node (ref "U4") (pin "7") (pinfunction "GPIO13_7") (pintype "passive"))
    )
    (net (code "152") (name "unconnected-(U4-GPIO14-Pad5)") (class "Default")
      (node (ref "U4") (pin "5") (pinfunction "GPIO14_5") (pintype "passive"))
    )
    (net (code "153") (name "unconnected-(U4-GPIO16-Pad4)") (class "Default")
      (node (ref "U4") (pin "4") (pinfunction "GPIO16_4") (pintype "passive"))
    )
    (net (code "154") (name "unconnected-(U4-MISO-Pad18)") (class "Default")
      (node (ref "U4") (pin "18") (pinfunction "MISO_18") (pintype "passive+no_connect"))
    )
    (net (code "155") (name "unconnected-(U4-MOSI-Pad21)") (class "Default")
      (node (ref "U4") (pin "21") (pinfunction "MOSI_21") (pintype "passive+no_connect"))
    )
    (net (code "156") (name "unconnected-(U4-SCLK-Pad22)") (class "Default")
      (node (ref "U4") (pin "22") (pinfunction "SCLK_22") (pintype "passive+no_connect"))
    )
    (net (code "157") (name "unconnected-(U5-GND-Pad15)") (class "Default")
      (node (ref "U5") (pin "15") (pinfunction "GND_15") (pintype "passive"))
    )
    (net (code "158") (name "unconnected-(U5-GPIO0-Pad5)") (class "Default")
      (node (ref "U5") (pin "5") (pinfunction "GPIO0_5") (pintype "passive+no_connect"))
    )
    (net (code "159") (name "unconnected-(U5-GPIO1-Pad4)") (class "Default")
      (node (ref "U5") (pin "4") (pinfunction "GPIO1_4") (pintype "passive+no_connect"))
    )
    (net (code "160") (name "unconnected-(U5-NC-Pad13)") (class "Default")
      (node (ref "U5") (pin "13") (pinfunction "NC_13") (pintype "passive+no_connect"))
    )
    (net (code "161") (name "unconnected-(U5-NC-Pad14)") (class "Default")
      (node (ref "U5") (pin "14") (pinfunction "NC_14") (pintype "passive+no_connect"))
    )
    (net (code "162") (name "unconnected-(U6-NC-Pad4)") (class "Default")
      (node (ref "U6") (pin "4") (pinfunction "NC_4") (pintype "passive+no_connect"))
    )
    (net (code "163") (name "unconnected-(U7-CTS#-Pad5)") (class "Default")
      (node (ref "U7") (pin "5") (pinfunction "CTS#_5") (pintype "passive"))
    )
    (net (code "164") (name "unconnected-(U7-RTS#-Pad4)") (class "Default")
      (node (ref "U7") (pin "4") (pinfunction "RTS#_4") (pintype "passive"))
    )
    (net (code "165") (name "unconnected-(U7-TNOW-Pad6)") (class "Default")
      (node (ref "U7") (pin "6") (pinfunction "TNOW_6") (pintype "passive"))
    )
    (net (code "166") (name "unconnected-(Y2-GND-Pad2)") (class "Default")
      (node (ref "Y2") (pin "2") (pinfunction "GND_2") (pintype "passive+no_connect"))
    )
    (net (code "167") (name "unconnected-(Y2-GND-Pad4)") (class "Default")
      (node (ref "Y2") (pin "4") (pinfunction "GND_4") (pintype "passive+no_connect"))
    )
  )
)
